# batsim1_1.net
KiCad netlist of a schematic drawn in EAGLE
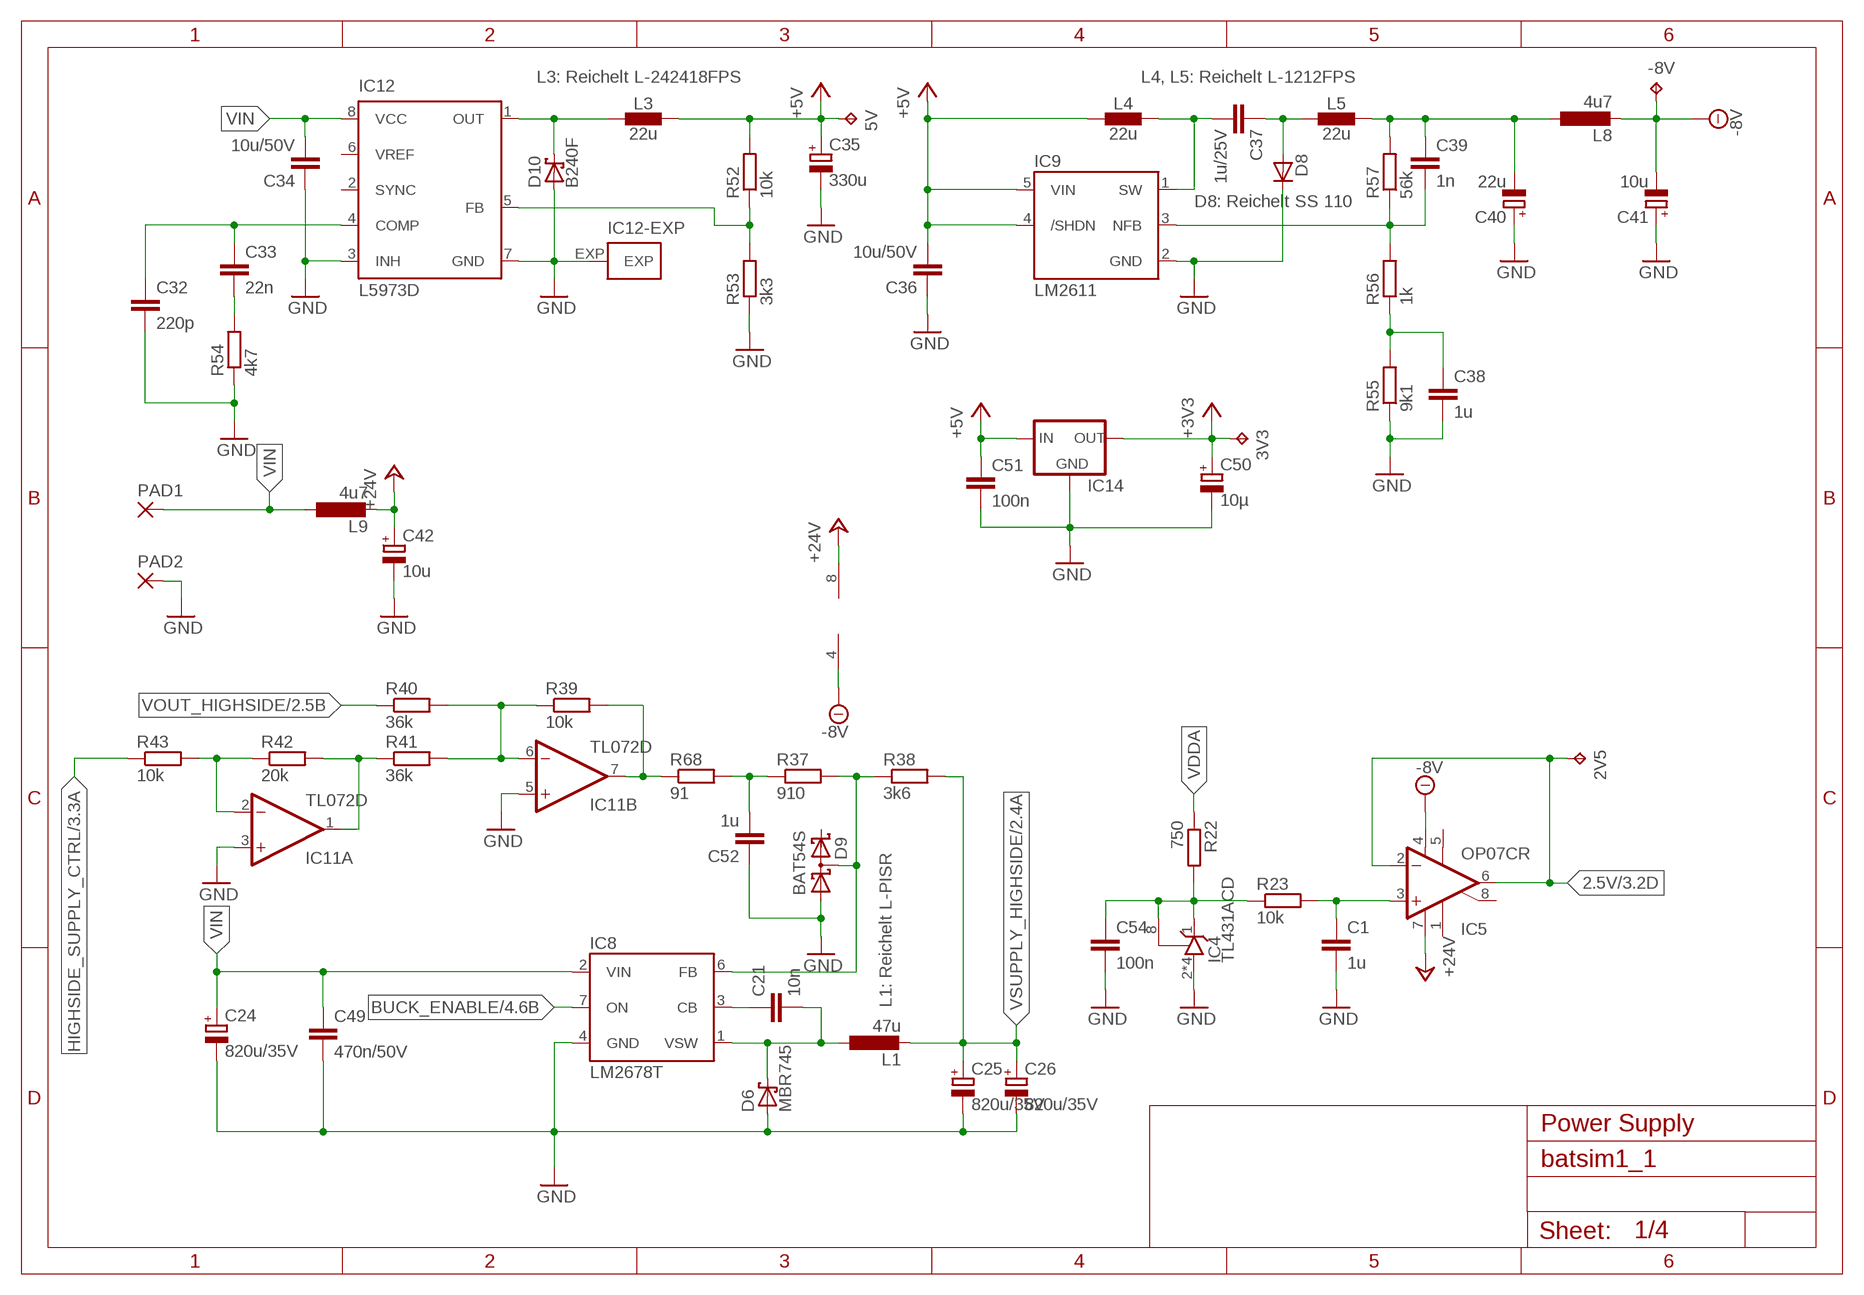
[diagram p0: schematic, sheet 1]
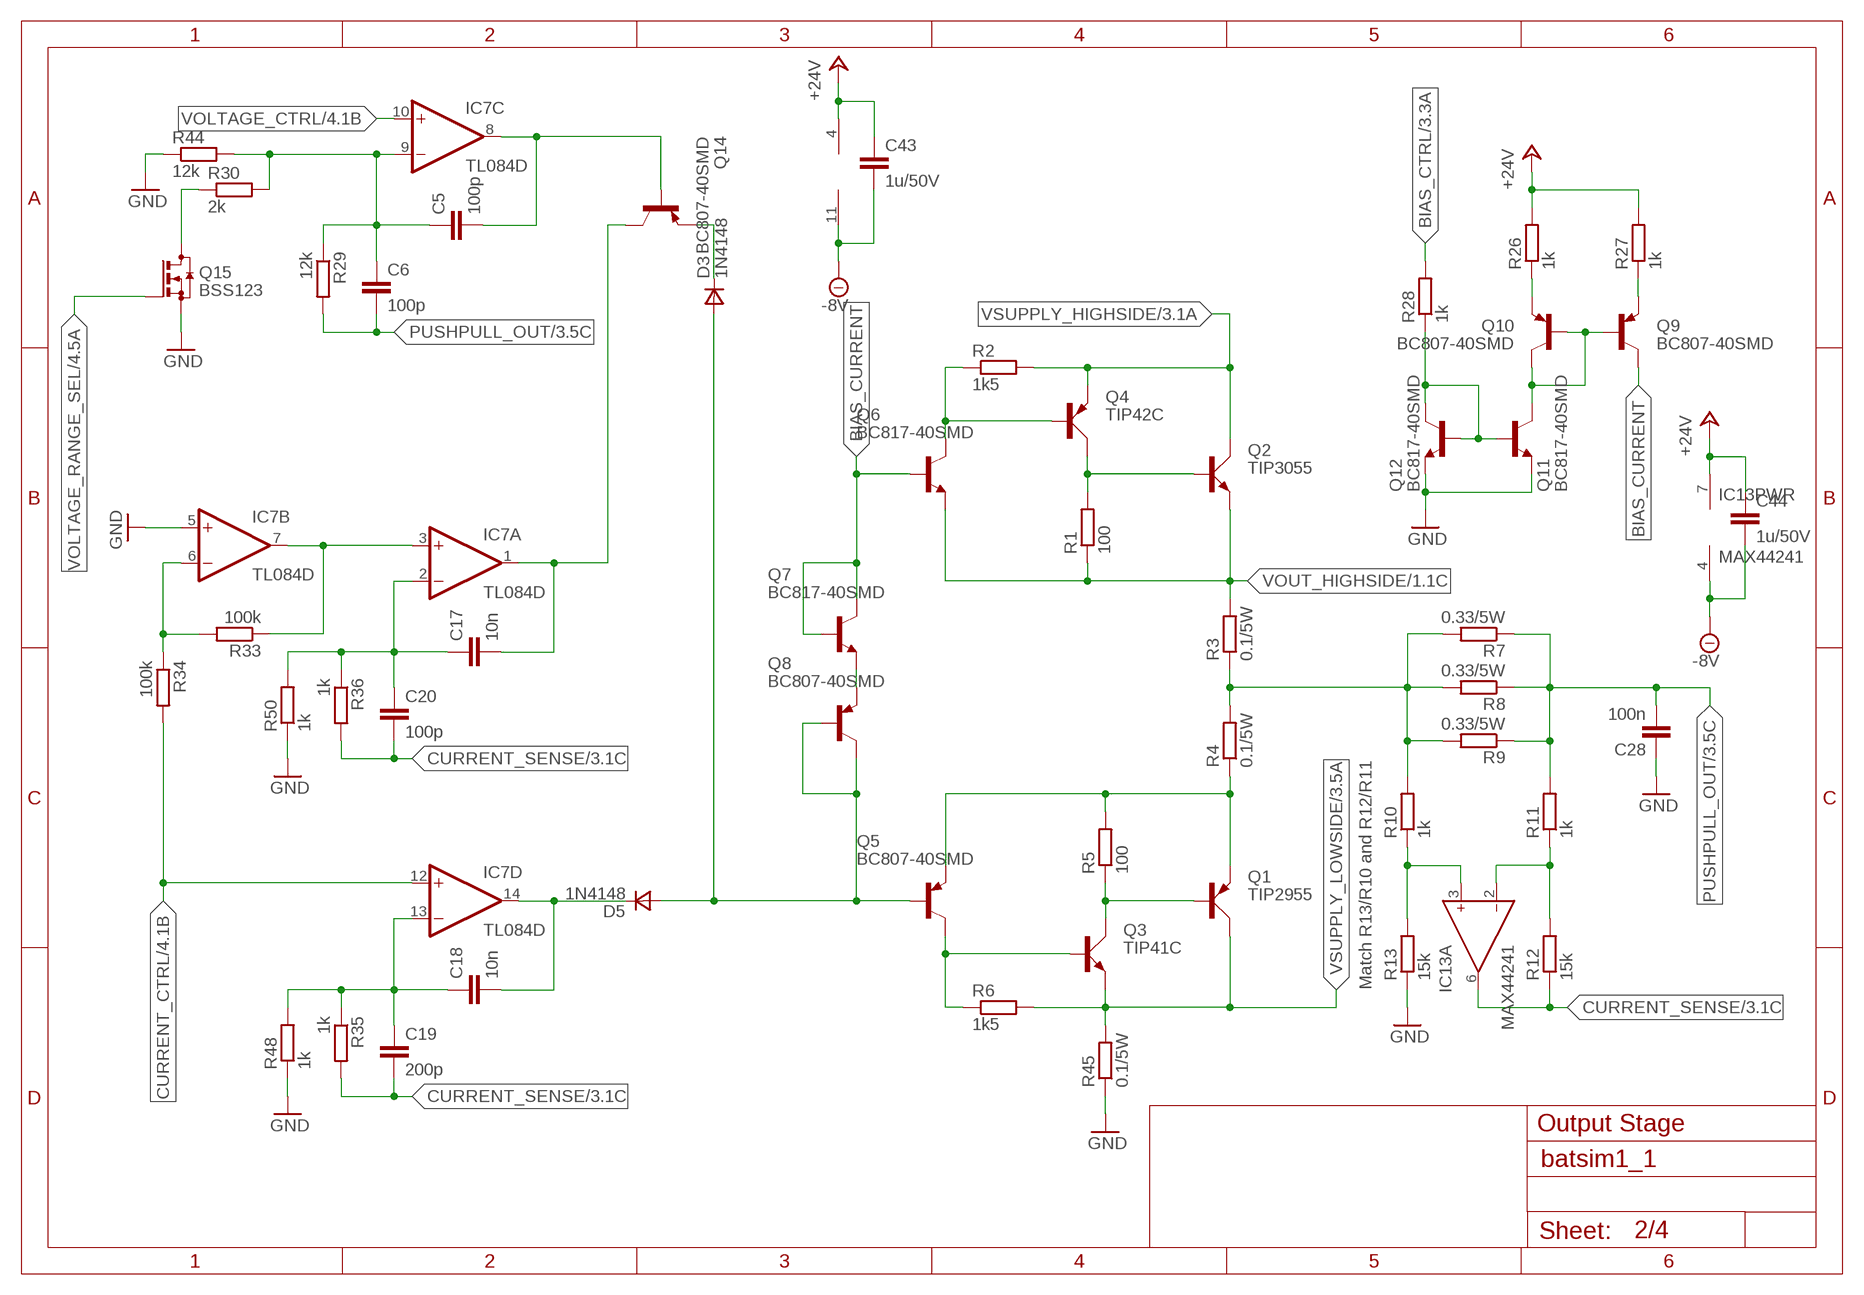
[diagram p1: schematic, sheet 2]
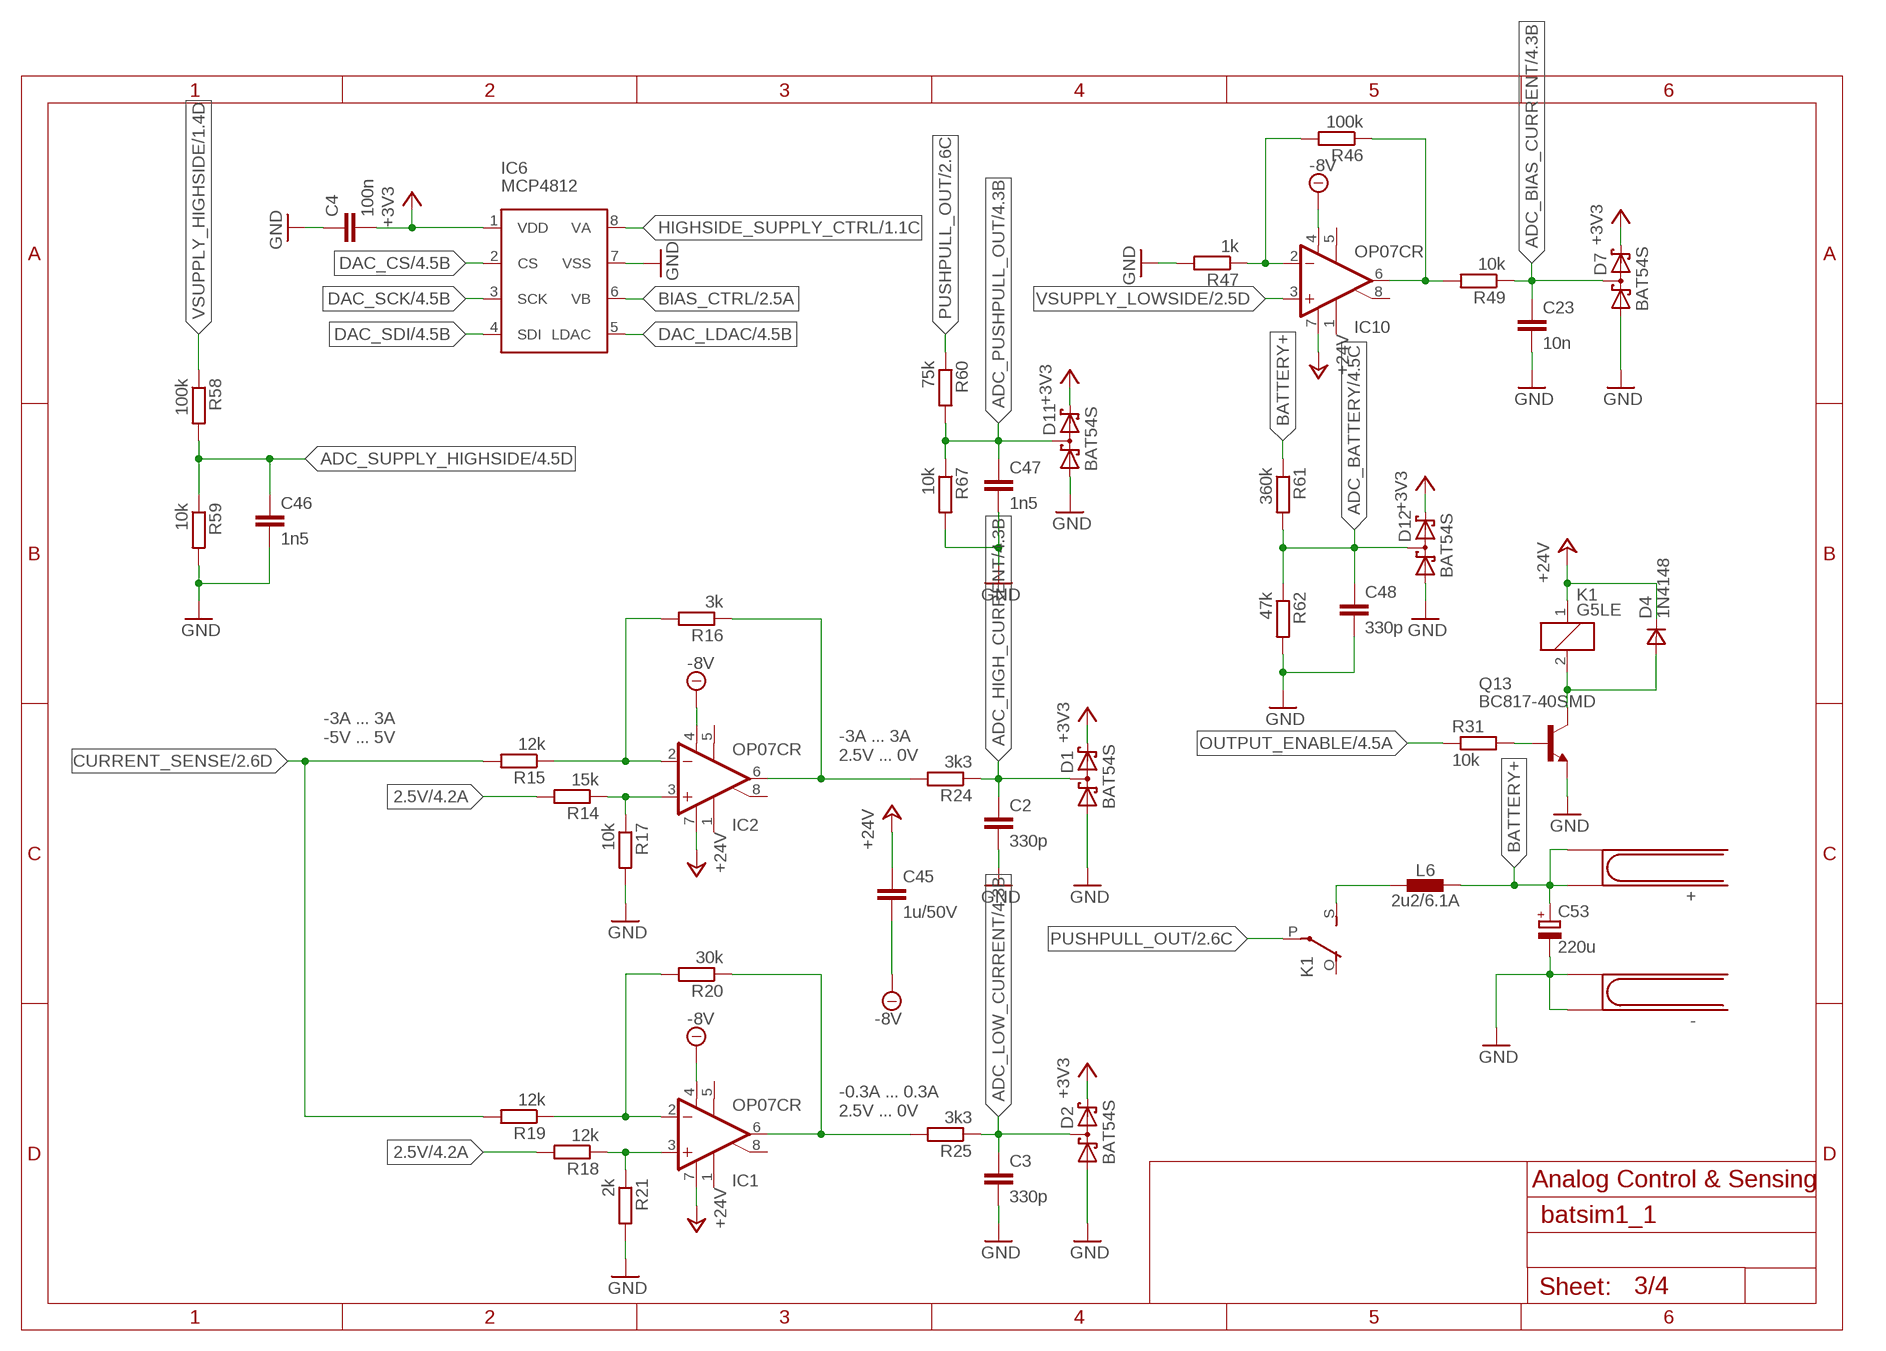
[diagram p2: schematic, sheet 3]
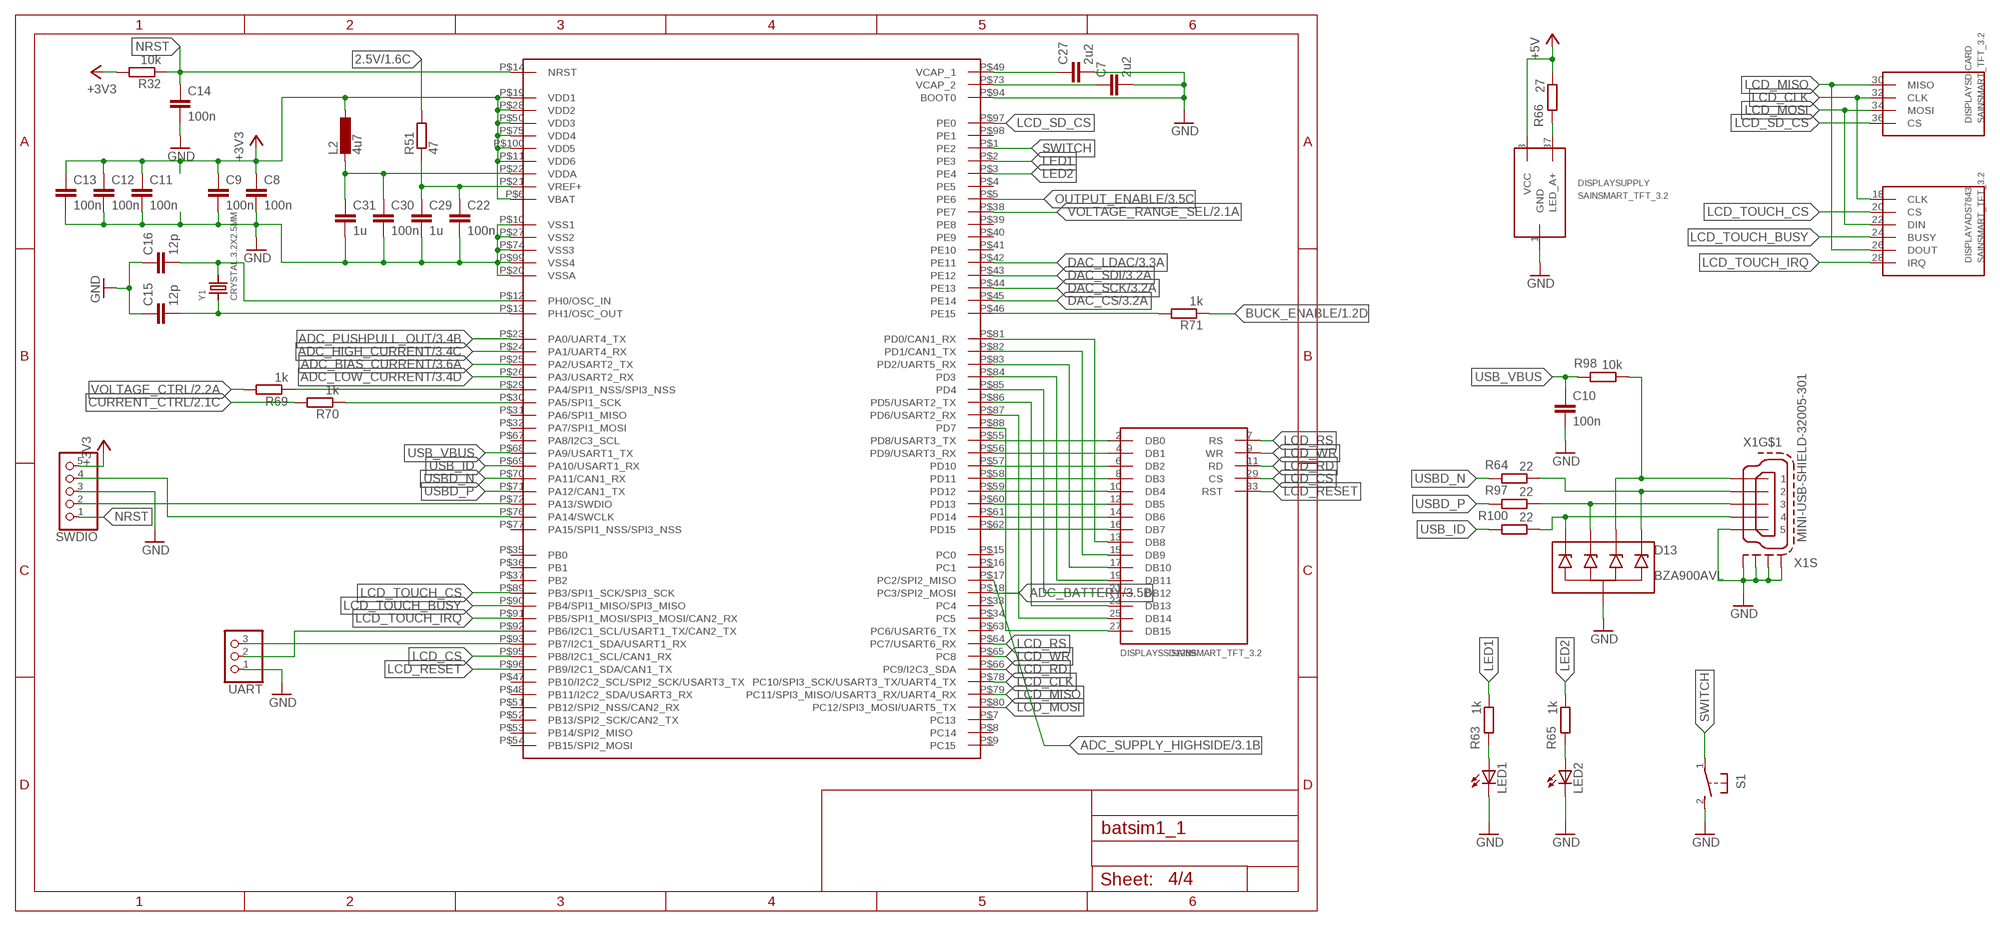
[diagram p3: schematic, sheet 4]

(export (version "E")
  (design (tool "Eeschema 10.0.6"))
  (components
    (comp (ref "+")
      (value "4MMJACK")
      (footprint "eagle-import:4MMJACK")
      (libsource (lib "eagle-import") (part "4MMJACK"))
    )
    (comp (ref "-")
      (value "4MMJACK")
      (footprint "eagle-import:4MMJACK")
      (libsource (lib "eagle-import") (part "4MMJACK"))
    )
    (comp (ref "C2")
      (value "330p")
      (footprint "eagle-import:C0603")
      (libsource (lib "eagle-import") (part "C-EUC0603"))
    )
    (comp (ref "C3")
      (value "330p")
      (footprint "eagle-import:C0603")
      (libsource (lib "eagle-import") (part "C-EUC0603"))
    )
    (comp (ref "C4")
      (value "100n")
      (footprint "eagle-import:C0603")
      (libsource (lib "eagle-import") (part "C-EUC0603"))
    )
    (comp (ref "C23")
      (value "10n")
      (footprint "eagle-import:C0603")
      (libsource (lib "eagle-import") (part "C-EUC0603"))
    )
    (comp (ref "C45")
      (value "1u/50V")
      (footprint "eagle-import:C0603")
      (libsource (lib "eagle-import") (part "C-EUC0603"))
    )
    (comp (ref "C46")
      (value "1n5")
      (footprint "eagle-import:C0603")
      (libsource (lib "eagle-import") (part "C-EUC0603"))
    )
    (comp (ref "C47")
      (value "1n5")
      (footprint "eagle-import:C0603")
      (libsource (lib "eagle-import") (part "C-EUC0603"))
    )
    (comp (ref "C48")
      (value "330p")
      (footprint "eagle-import:C0603")
      (libsource (lib "eagle-import") (part "C-EUC0603"))
    )
    (comp (ref "C53")
      (value "220u")
      (footprint "eagle-import:E5-10,5")
      (libsource (lib "eagle-import") (part "resistor_CPOL-EUE5-10.5"))
    )
    (comp (ref "D1")
      (value "BAT54S")
      (footprint "eagle-import:SOT23")
      (libsource (lib "eagle-import") (part "BAT54S"))
    )
    (comp (ref "D2")
      (value "BAT54S")
      (footprint "eagle-import:SOT23")
      (libsource (lib "eagle-import") (part "BAT54S"))
    )
    (comp (ref "D4")
      (value "1N4148")
      (footprint "eagle-import:SOD323")
      (fields (field (name "MPN") "CDSOD323-T05C"))
      (libsource (lib "eagle-import") (part "DSOD323"))
    )
    (comp (ref "D7")
      (value "BAT54S")
      (footprint "eagle-import:SOT23")
      (libsource (lib "eagle-import") (part "BAT54S"))
    )
    (comp (ref "D11")
      (value "BAT54S")
      (footprint "eagle-import:SOT23")
      (libsource (lib "eagle-import") (part "BAT54S"))
    )
    (comp (ref "D12")
      (value "BAT54S")
      (footprint "eagle-import:SOT23")
      (libsource (lib "eagle-import") (part "BAT54S"))
    )
    (comp (ref "IC1")
      (value "OP07CR")
      (footprint "eagle-import:SO08")
      (libsource (lib "eagle-import") (part "OP07RC"))
    )
    (comp (ref "IC2")
      (value "OP07CR")
      (footprint "eagle-import:SO08")
      (libsource (lib "eagle-import") (part "OP07RC"))
    )
    (comp (ref "IC6")
      (value "MCP4812")
      (footprint "eagle-import:SO08")
      (fields (field (name "MPN") "MCP4822-E/SN"))
      (libsource (lib "eagle-import") (part "MCP4812"))
    )
    (comp (ref "IC10")
      (value "OP07CR")
      (footprint "eagle-import:SO08")
      (libsource (lib "eagle-import") (part "OP07RC"))
    )
    (comp (ref "K1")
      (value "G5LE")
      (footprint "eagle-import:G5LE")
      (libsource (lib "eagle-import") (part "G5LE"))
    )
    (comp (ref "L6")
      (value "2u2/6.1A")
      (footprint "eagle-import:L_NR60XX")
      (libsource (lib "eagle-import") (part "INDUCTOR-NR60XX"))
    )
    (comp (ref "Q13")
      (value "BC817-40SMD")
      (footprint "eagle-import:SOT23-BEC")
      (libsource (lib "eagle-import") (part "BC817SMD-40"))
    )
    (comp (ref "R14")
      (value "15k")
      (footprint "eagle-import:R0603")
      (libsource (lib "eagle-import") (part "R-EU_R0603"))
    )
    (comp (ref "R15")
      (value "12k")
      (footprint "eagle-import:R0603")
      (libsource (lib "eagle-import") (part "R-EU_R0603"))
    )
    (comp (ref "R16")
      (value "3k")
      (footprint "eagle-import:R0603")
      (libsource (lib "eagle-import") (part "R-EU_R0603"))
    )
    (comp (ref "R17")
      (value "10k")
      (footprint "eagle-import:R0603")
      (libsource (lib "eagle-import") (part "R-EU_R0603"))
    )
    (comp (ref "R18")
      (value "12k")
      (footprint "eagle-import:R0603")
      (libsource (lib "eagle-import") (part "R-EU_R0603"))
    )
    (comp (ref "R19")
      (value "12k")
      (footprint "eagle-import:R0603")
      (libsource (lib "eagle-import") (part "R-EU_R0603"))
    )
    (comp (ref "R20")
      (value "30k")
      (footprint "eagle-import:R0603")
      (libsource (lib "eagle-import") (part "R-EU_R0603"))
    )
    (comp (ref "R21")
      (value "2k")
      (footprint "eagle-import:R0603")
      (libsource (lib "eagle-import") (part "R-EU_R0603"))
    )
    (comp (ref "R24")
      (value "3k3")
      (footprint "eagle-import:R0603")
      (libsource (lib "eagle-import") (part "R-EU_R0603"))
    )
    (comp (ref "R25")
      (value "3k3")
      (footprint "eagle-import:R0603")
      (libsource (lib "eagle-import") (part "R-EU_R0603"))
    )
    (comp (ref "R31")
      (value "10k")
      (footprint "eagle-import:R0603")
      (libsource (lib "eagle-import") (part "R-EU_R0603"))
    )
    (comp (ref "R46")
      (value "100k")
      (footprint "eagle-import:R0603")
      (libsource (lib "eagle-import") (part "R-EU_R0603"))
    )
    (comp (ref "R47")
      (value "1k")
      (footprint "eagle-import:R0603")
      (libsource (lib "eagle-import") (part "R-EU_R0603"))
    )
    (comp (ref "R49")
      (value "10k")
      (footprint "eagle-import:R0603")
      (libsource (lib "eagle-import") (part "R-EU_R0603"))
    )
    (comp (ref "R58")
      (value "100k")
      (footprint "eagle-import:R0603")
      (libsource (lib "eagle-import") (part "R-EU_R0603"))
    )
    (comp (ref "R59")
      (value "10k")
      (footprint "eagle-import:R0603")
      (libsource (lib "eagle-import") (part "R-EU_R0603"))
    )
    (comp (ref "R60")
      (value "75k")
      (footprint "eagle-import:R0603")
      (libsource (lib "eagle-import") (part "R-EU_R0603"))
    )
    (comp (ref "R61")
      (value "360k")
      (footprint "eagle-import:R0603")
      (libsource (lib "eagle-import") (part "R-EU_R0603"))
    )
    (comp (ref "R62")
      (value "47k")
      (footprint "eagle-import:R0603")
      (libsource (lib "eagle-import") (part "R-EU_R0603"))
    )
    (comp (ref "R67")
      (value "10k")
      (footprint "eagle-import:R0603")
      (libsource (lib "eagle-import") (part "R-EU_R0603"))
    )
    (comp (ref "C7")
      (value "2u2")
      (footprint "eagle-import:C1206")
      (libsource (lib "eagle-import") (part "C-EUC1206"))
    )
    (comp (ref "C8")
      (value "100n")
      (footprint "eagle-import:C0603")
      (libsource (lib "eagle-import") (part "C-EUC0603"))
    )
    (comp (ref "C9")
      (value "100n")
      (footprint "eagle-import:C0603")
      (libsource (lib "eagle-import") (part "C-EUC0603"))
    )
    (comp (ref "C10")
      (value "100n")
      (footprint "eagle-import:C0603K")
      (libsource (lib "eagle-import") (part "C-EUC0603K"))
    )
    (comp (ref "C11")
      (value "100n")
      (footprint "eagle-import:C0603")
      (libsource (lib "eagle-import") (part "C-EUC0603"))
    )
    (comp (ref "C12")
      (value "100n")
      (footprint "eagle-import:C0603")
      (libsource (lib "eagle-import") (part "C-EUC0603"))
    )
    (comp (ref "C13")
      (value "100n")
      (footprint "eagle-import:C0603")
      (libsource (lib "eagle-import") (part "C-EUC0603"))
    )
    (comp (ref "C14")
      (value "100n")
      (footprint "eagle-import:C0603")
      (libsource (lib "eagle-import") (part "C-EUC0603"))
    )
    (comp (ref "C15")
      (value "12p")
      (footprint "eagle-import:C0603")
      (libsource (lib "eagle-import") (part "C-EUC0603"))
    )
    (comp (ref "C16")
      (value "12p")
      (footprint "eagle-import:C0603")
      (libsource (lib "eagle-import") (part "C-EUC0603"))
    )
    (comp (ref "C22")
      (value "100n")
      (footprint "eagle-import:C0603")
      (libsource (lib "eagle-import") (part "C-EUC0603"))
    )
    (comp (ref "C27")
      (value "2u2")
      (footprint "eagle-import:C1206")
      (libsource (lib "eagle-import") (part "C-EUC1206"))
    )
    (comp (ref "C29")
      (value "1u")
      (footprint "eagle-import:C0603")
      (libsource (lib "eagle-import") (part "C-EUC0603"))
    )
    (comp (ref "C30")
      (value "100n")
      (footprint "eagle-import:C0603")
      (libsource (lib "eagle-import") (part "C-EUC0603"))
    )
    (comp (ref "C31")
      (value "1u")
      (footprint "eagle-import:C0603")
      (libsource (lib "eagle-import") (part "C-EUC0603"))
    )
    (comp (ref "D13")
      (value "BZA900AVL")
      (footprint "eagle-import:SOT-665")
      (libsource (lib "eagle-import") (part "BZA900AVL"))
    )
    (comp (ref "DISPLAY")
      (value "SAINSMART_TFT_3.2")
      (footprint "eagle-import:SAINSMART_TFT_3.2")
      (libsource (lib "eagle-import") (part "SAINSMART_TFT_3.2"))
    )
    (comp (ref "L2")
      (value "4u7")
      (footprint "eagle-import:L2012C")
      (libsource (lib "eagle-import") (part "L-EUL2012C"))
    )
    (comp (ref "LED1")
      (value "LEDCHIP-LED0603")
      (footprint "eagle-import:CHIP-LED0603")
      (libsource (lib "eagle-import") (part "LEDCHIP-LED0603"))
    )
    (comp (ref "LED2")
      (value "LEDCHIP-LED0603")
      (footprint "eagle-import:CHIP-LED0603")
      (libsource (lib "eagle-import") (part "LEDCHIP-LED0603"))
    )
    (comp (ref "R32")
      (value "10k")
      (footprint "eagle-import:R0603")
      (libsource (lib "eagle-import") (part "R-EU_R0603"))
    )
    (comp (ref "R51")
      (value "47")
      (footprint "eagle-import:R0603")
      (libsource (lib "eagle-import") (part "R-EU_R0603"))
    )
    (comp (ref "R63")
      (value "1k")
      (footprint "eagle-import:R0603")
      (libsource (lib "eagle-import") (part "R-EU_R0603"))
    )
    (comp (ref "R64")
      (value "22")
      (footprint "eagle-import:R0603")
      (libsource (lib "eagle-import") (part "R-EU_R0603"))
    )
    (comp (ref "R65")
      (value "1k")
      (footprint "eagle-import:R0603")
      (libsource (lib "eagle-import") (part "R-EU_R0603"))
    )
    (comp (ref "R66")
      (value "27")
      (footprint "eagle-import:R0603")
      (libsource (lib "eagle-import") (part "R-EU_R0603"))
    )
    (comp (ref "R69")
      (value "1k")
      (footprint "eagle-import:R0603")
      (libsource (lib "eagle-import") (part "R-EU_R0603"))
    )
    (comp (ref "R70")
      (value "1k")
      (footprint "eagle-import:R0603")
      (libsource (lib "eagle-import") (part "R-EU_R0603"))
    )
    (comp (ref "R71")
      (value "1k")
      (footprint "eagle-import:R0603")
      (libsource (lib "eagle-import") (part "R-EU_R0603"))
    )
    (comp (ref "R97")
      (value "22")
      (footprint "eagle-import:R0603")
      (libsource (lib "eagle-import") (part "R-EU_R0603"))
    )
    (comp (ref "R98")
      (value "10k")
      (footprint "eagle-import:R0603")
      (libsource (lib "eagle-import") (part "R-EU_R0603"))
    )
    (comp (ref "R100")
      (value "22")
      (footprint "eagle-import:R0603")
      (libsource (lib "eagle-import") (part "R-EU_R0603"))
    )
    (comp (ref "S1")
      (value "31-XX")
      (footprint "eagle-import:B3F-31XX")
      (fields (field (name "MPN") "B3F-3100"))
      (libsource (lib "eagle-import") (part "31-XX"))
    )
    (comp (ref "SWDIO")
      (value "PINHD-1X5")
      (footprint "eagle-import:1X05")
      (libsource (lib "eagle-import") (part "PINHD-1X5"))
    )
    (comp (ref "U$1")
      (value "STM32F407X100")
      (footprint "eagle-import:LQFP100_14")
      (libsource (lib "eagle-import") (part "STM32F407X100"))
    )
    (comp (ref "UART")
      (value "PINHD-1X3")
      (footprint "eagle-import:1X03")
      (libsource (lib "eagle-import") (part "PINHD-1X3"))
    )
    (comp (ref "X1")
      (value "MINI-USB-SHIELD-32005-301")
      (footprint "eagle-import:32005-301")
      (libsource (lib "eagle-import") (part "MINI-USB-SCHIELD-32005-301"))
    )
    (comp (ref "Y1")
      (value "CRYSTAL.3.2X2.5MM")
      (footprint "eagle-import:3.2X2.5MM")
      (libsource (lib "eagle-import") (part "CRYSTAL.3.2X2.5MM"))
    )
    (comp (ref "C5")
      (value "100p")
      (footprint "eagle-import:C0603")
      (libsource (lib "eagle-import") (part "C-EUC0603"))
    )
    (comp (ref "C6")
      (value "100p")
      (footprint "eagle-import:C0603")
      (libsource (lib "eagle-import") (part "C-EUC0603"))
    )
    (comp (ref "C17")
      (value "10n")
      (footprint "eagle-import:C0603")
      (libsource (lib "eagle-import") (part "C-EUC0603"))
    )
    (comp (ref "C18")
      (value "10n")
      (footprint "eagle-import:C0603")
      (libsource (lib "eagle-import") (part "C-EUC0603"))
    )
    (comp (ref "C19")
      (value "200p")
      (footprint "eagle-import:C0603")
      (libsource (lib "eagle-import") (part "C-EUC0603"))
    )
    (comp (ref "C20")
      (value "100p")
      (footprint "eagle-import:C0603")
      (libsource (lib "eagle-import") (part "C-EUC0603"))
    )
    (comp (ref "C28")
      (value "100n")
      (footprint "eagle-import:C1206")
      (libsource (lib "eagle-import") (part "C-EUC1206"))
    )
    (comp (ref "C43")
      (value "1u/50V")
      (footprint "eagle-import:C0603")
      (libsource (lib "eagle-import") (part "C-EUC0603"))
    )
    (comp (ref "C44")
      (value "1u/50V")
      (footprint "eagle-import:C0603")
      (libsource (lib "eagle-import") (part "C-EUC0603"))
    )
    (comp (ref "D3")
      (value "1N4148")
      (footprint "eagle-import:SOD323")
      (fields (field (name "MPN") "CDSOD323-T05C"))
      (libsource (lib "eagle-import") (part "DSOD323"))
    )
    (comp (ref "D5")
      (value "1N4148")
      (footprint "eagle-import:SOD323")
      (fields (field (name "MPN") "CDSOD323-T05C"))
      (libsource (lib "eagle-import") (part "DSOD323"))
    )
    (comp (ref "IC7")
      (value "TL084D")
      (footprint "eagle-import:SO14")
      (libsource (lib "eagle-import") (part "TL084D"))
    )
    (comp (ref "IC13")
      (value "MAX44241")
      (footprint "eagle-import:UMAX8")
      (libsource (lib "eagle-import") (part "MAX44241"))
    )
    (comp (ref "Q1")
      (value "TIP2955")
      (footprint "eagle-import:TOP3AV")
      (libsource (lib "eagle-import") (part "TIP2955"))
    )
    (comp (ref "Q2")
      (value "TIP3055")
      (footprint "eagle-import:TOP3AV")
      (libsource (lib "eagle-import") (part "TIP3055"))
    )
    (comp (ref "Q3")
      (value "TIP41C")
      (footprint "eagle-import:TO220AV")
      (libsource (lib "eagle-import") (part "TIP41C"))
    )
    (comp (ref "Q4")
      (value "TIP42C")
      (footprint "eagle-import:TO220AV")
      (libsource (lib "eagle-import") (part "TIP42C"))
    )
    (comp (ref "Q5")
      (value "BC807-40SMD")
      (footprint "eagle-import:SOT23-BEC")
      (libsource (lib "eagle-import") (part "BC807SMD-40"))
    )
    (comp (ref "Q6")
      (value "BC817-40SMD")
      (footprint "eagle-import:SOT23-BEC")
      (libsource (lib "eagle-import") (part "BC817SMD-40"))
    )
    (comp (ref "Q7")
      (value "BC817-40SMD")
      (footprint "eagle-import:SOT23-BEC")
      (libsource (lib "eagle-import") (part "BC817SMD-40"))
    )
    (comp (ref "Q8")
      (value "BC807-40SMD")
      (footprint "eagle-import:SOT23-BEC")
      (libsource (lib "eagle-import") (part "BC807SMD-40"))
    )
    (comp (ref "Q9")
      (value "BC807-40SMD")
      (footprint "eagle-import:SOT23-BEC")
      (libsource (lib "eagle-import") (part "BC807SMD-40"))
    )
    (comp (ref "Q10")
      (value "BC807-40SMD")
      (footprint "eagle-import:SOT23-BEC")
      (libsource (lib "eagle-import") (part "BC807SMD-40"))
    )
    (comp (ref "Q11")
      (value "BC817-40SMD")
      (footprint "eagle-import:SOT23-BEC")
      (libsource (lib "eagle-import") (part "BC817SMD-40"))
    )
    (comp (ref "Q12")
      (value "BC817-40SMD")
      (footprint "eagle-import:SOT23-BEC")
      (libsource (lib "eagle-import") (part "BC817SMD-40"))
    )
    (comp (ref "Q14")
      (value "BC807-40SMD")
      (footprint "eagle-import:SOT23-BEC")
      (libsource (lib "eagle-import") (part "BC807SMD-40"))
    )
    (comp (ref "Q15")
      (value "BSS123")
      (footprint "eagle-import:SOT23")
      (libsource (lib "eagle-import") (part "BSS123"))
    )
    (comp (ref "R1")
      (value "100")
      (footprint "eagle-import:R0603")
      (libsource (lib "eagle-import") (part "R-EU_R0603"))
    )
    (comp (ref "R2")
      (value "1k5")
      (footprint "eagle-import:R0603")
      (libsource (lib "eagle-import") (part "R-EU_R0603"))
    )
    (comp (ref "R3")
      (value "0.1/5W")
      (footprint "eagle-import:5WAXIAL")
      (libsource (lib "eagle-import") (part "5WAXIAL"))
    )
    (comp (ref "R4")
      (value "0.1/5W")
      (footprint "eagle-import:5WAXIAL")
      (libsource (lib "eagle-import") (part "5WAXIAL"))
    )
    (comp (ref "R5")
      (value "100")
      (footprint "eagle-import:R0603")
      (libsource (lib "eagle-import") (part "R-EU_R0603"))
    )
    (comp (ref "R6")
      (value "1k5")
      (footprint "eagle-import:R0603")
      (libsource (lib "eagle-import") (part "R-EU_R0603"))
    )
    (comp (ref "R7")
      (value "0.33/5W")
      (footprint "eagle-import:5WAXIAL")
      (libsource (lib "eagle-import") (part "5WAXIAL"))
    )
    (comp (ref "R8")
      (value "0.33/5W")
      (footprint "eagle-import:5WAXIAL")
      (libsource (lib "eagle-import") (part "5WAXIAL"))
    )
    (comp (ref "R9")
      (value "0.33/5W")
      (footprint "eagle-import:5WAXIAL")
      (libsource (lib "eagle-import") (part "5WAXIAL"))
    )
    (comp (ref "R10")
      (value "1k")
      (footprint "eagle-import:R0603")
      (libsource (lib "eagle-import") (part "R-EU_R0603"))
    )
    (comp (ref "R11")
      (value "1k")
      (footprint "eagle-import:R0603")
      (libsource (lib "eagle-import") (part "R-EU_R0603"))
    )
    (comp (ref "R12")
      (value "15k")
      (footprint "eagle-import:R0603")
      (libsource (lib "eagle-import") (part "R-EU_R0603"))
    )
    (comp (ref "R13")
      (value "15k")
      (footprint "eagle-import:R0603")
      (libsource (lib "eagle-import") (part "R-EU_R0603"))
    )
    (comp (ref "R26")
      (value "1k")
      (footprint "eagle-import:R0603")
      (libsource (lib "eagle-import") (part "R-EU_R0603"))
    )
    (comp (ref "R27")
      (value "1k")
      (footprint "eagle-import:R0603")
      (libsource (lib "eagle-import") (part "R-EU_R0603"))
    )
    (comp (ref "R28")
      (value "1k")
      (footprint "eagle-import:R0603")
      (libsource (lib "eagle-import") (part "R-EU_R0603"))
    )
    (comp (ref "R29")
      (value "12k")
      (footprint "eagle-import:R0603")
      (libsource (lib "eagle-import") (part "R-EU_R0603"))
    )
    (comp (ref "R30")
      (value "2k")
      (footprint "eagle-import:R0603")
      (libsource (lib "eagle-import") (part "R-EU_R0603"))
    )
    (comp (ref "R33")
      (value "100k")
      (footprint "eagle-import:R0603")
      (libsource (lib "eagle-import") (part "R-EU_R0603"))
    )
    (comp (ref "R34")
      (value "100k")
      (footprint "eagle-import:R0603")
      (libsource (lib "eagle-import") (part "R-EU_R0603"))
    )
    (comp (ref "R35")
      (value "1k")
      (footprint "eagle-import:R0603")
      (libsource (lib "eagle-import") (part "R-EU_R0603"))
    )
    (comp (ref "R36")
      (value "1k")
      (footprint "eagle-import:R0603")
      (libsource (lib "eagle-import") (part "R-EU_R0603"))
    )
    (comp (ref "R44")
      (value "12k")
      (footprint "eagle-import:R0603")
      (libsource (lib "eagle-import") (part "R-EU_R0603"))
    )
    (comp (ref "R45")
      (value "0.1/5W")
      (footprint "eagle-import:5WAXIAL")
      (libsource (lib "eagle-import") (part "5WAXIAL"))
    )
    (comp (ref "R48")
      (value "1k")
      (footprint "eagle-import:R0603")
      (libsource (lib "eagle-import") (part "R-EU_R0603"))
    )
    (comp (ref "R50")
      (value "1k")
      (footprint "eagle-import:R0603")
      (libsource (lib "eagle-import") (part "R-EU_R0603"))
    )
    (comp (ref "-8V")
      (value "TPB1,27")
      (footprint "eagle-import:B1,27")
      (libsource (lib "eagle-import") (part "TPB1,27"))
    )
    (comp (ref "2V5")
      (value "TPB1,27")
      (footprint "eagle-import:B1,27")
      (libsource (lib "eagle-import") (part "TPB1,27"))
    )
    (comp (ref "3V3")
      (value "TPB1,27")
      (footprint "eagle-import:B1,27")
      (libsource (lib "eagle-import") (part "TPB1,27"))
    )
    (comp (ref "5V")
      (value "TPB1,27")
      (footprint "eagle-import:B1,27")
      (libsource (lib "eagle-import") (part "TPB1,27"))
    )
    (comp (ref "C1")
      (value "1u")
      (footprint "eagle-import:C0603")
      (libsource (lib "eagle-import") (part "C-EUC0603"))
    )
    (comp (ref "C21")
      (value "10n")
      (footprint "eagle-import:C0603")
      (libsource (lib "eagle-import") (part "C-EUC0603"))
    )
    (comp (ref "C24")
      (value "820u/35V")
      (footprint "eagle-import:E5-10,5")
      (libsource (lib "eagle-import") (part "resistor_CPOL-EUE5-10.5"))
    )
    (comp (ref "C25")
      (value "820u/35V")
      (footprint "eagle-import:E5-10,5")
      (libsource (lib "eagle-import") (part "resistor_CPOL-EUE5-10.5"))
    )
    (comp (ref "C26")
      (value "820u/35V")
      (footprint "eagle-import:E5-10,5")
      (libsource (lib "eagle-import") (part "resistor_CPOL-EUE5-10.5"))
    )
    (comp (ref "C32")
      (value "220p")
      (footprint "eagle-import:C0603")
      (libsource (lib "eagle-import") (part "C-EUC0603"))
    )
    (comp (ref "C33")
      (value "22n")
      (footprint "eagle-import:C0603")
      (libsource (lib "eagle-import") (part "C-EUC0603"))
    )
    (comp (ref "C34")
      (value "10u/50V")
      (footprint "eagle-import:C1206")
      (libsource (lib "eagle-import") (part "C-EUC1206"))
    )
    (comp (ref "C35")
      (value "330u")
      (footprint "eagle-import:153CLV-0605")
      (libsource (lib "eagle-import") (part "resistor_CPOL-EU153CLV-0605"))
    )
    (comp (ref "C36")
      (value "10u/50V")
      (footprint "eagle-import:C1206")
      (libsource (lib "eagle-import") (part "C-EUC1206"))
    )
    (comp (ref "C37")
      (value "1u/25V")
      (footprint "eagle-import:C1206")
      (libsource (lib "eagle-import") (part "C-EUC1206"))
    )
    (comp (ref "C38")
      (value "1u")
      (footprint "eagle-import:C0603")
      (libsource (lib "eagle-import") (part "C-EUC0603"))
    )
    (comp (ref "C39")
      (value "1n")
      (footprint "eagle-import:C0603")
      (libsource (lib "eagle-import") (part "C-EUC0603"))
    )
    (comp (ref "C40")
      (value "22u")
      (footprint "eagle-import:153CLV-0505")
      (libsource (lib "eagle-import") (part "resistor_CPOL-EU153CLV-0505"))
    )
    (comp (ref "C41")
      (value "10u")
      (footprint "eagle-import:153CLV-0405")
      (libsource (lib "eagle-import") (part "resistor_CPOL-EU153CLV-0405"))
    )
    (comp (ref "C42")
      (value "10u")
      (footprint "eagle-import:153CLV-0505")
      (libsource (lib "eagle-import") (part "resistor_CPOL-EU153CLV-0505"))
    )
    (comp (ref "C49")
      (value "470n/50V")
      (footprint "eagle-import:C1206")
      (libsource (lib "eagle-import") (part "C-EUC1206"))
    )
    (comp (ref "C50")
      (value "10µ")
      (footprint "eagle-import:SMC_A")
      (libsource (lib "eagle-import") (part "CPOL-EUSMCA"))
    )
    (comp (ref "C51")
      (value "100n")
      (footprint "eagle-import:C0603")
      (libsource (lib "eagle-import") (part "C-EUC0603"))
    )
    (comp (ref "C52")
      (value "1u")
      (footprint "eagle-import:C0603")
      (libsource (lib "eagle-import") (part "C-EUC0603"))
    )
    (comp (ref "C54")
      (value "100n")
      (footprint "eagle-import:C0603")
      (libsource (lib "eagle-import") (part "C-EUC0603"))
    )
    (comp (ref "D6")
      (value "MBR745")
      (footprint "eagle-import:TO220ACS")
      (libsource (lib "eagle-import") (part "MBR745"))
    )
    (comp (ref "D8")
      (value "D-SMA")
      (footprint "eagle-import:SMA")
      (libsource (lib "eagle-import") (part "D-SMA"))
    )
    (comp (ref "D9")
      (value "BAT54S")
      (footprint "eagle-import:SOT23")
      (libsource (lib "eagle-import") (part "BAT54S"))
    )
    (comp (ref "D10")
      (value "B240F")
      (footprint "eagle-import:SMB")
      (libsource (lib "eagle-import") (part "SCHOTTKY-DIODESMD"))
    )
    (comp (ref "IC4")
      (value "TL431ACD")
      (footprint "eagle-import:SO8")
      (libsource (lib "eagle-import") (part "TL431ACD"))
    )
    (comp (ref "IC5")
      (value "OP07CR")
      (footprint "eagle-import:SO08")
      (libsource (lib "eagle-import") (part "OP07RC"))
    )
    (comp (ref "IC8")
      (value "LM2678T")
      (footprint "eagle-import:TO220-7")
      (libsource (lib "eagle-import") (part "LM2678T"))
    )
    (comp (ref "IC9")
      (value "LM2611")
      (footprint "eagle-import:SOT23-5")
      (libsource (lib "eagle-import") (part "LM2611"))
    )
    (comp (ref "IC11")
      (value "TL072D")
      (footprint "eagle-import:SO08")
      (libsource (lib "eagle-import") (part "TL072D"))
    )
    (comp (ref "IC12")
      (value "L5973D")
      (footprint "eagle-import:HSOP8")
      (fields (field (name "MF") "STMICROELECTRONICS"))
      (libsource (lib "eagle-import") (part "L5973D"))
    )
    (comp (ref "IC14")
      (value "LM1117")
      (footprint "eagle-import:SOT223")
      (libsource (lib "eagle-import") (part "LM1117"))
    )
    (comp (ref "L1")
      (value "47u")
      (footprint "eagle-import:PISR")
      (libsource (lib "eagle-import") (part "L-EUPISR"))
    )
    (comp (ref "L3")
      (value "22u")
      (footprint "eagle-import:L_NR60XX")
      (libsource (lib "eagle-import") (part "INDUCTOR-NR60XX"))
    )
    (comp (ref "L4")
      (value "22u")
      (footprint "eagle-import:L_1212")
      (libsource (lib "eagle-import") (part "INDUCTOR-1212"))
    )
    (comp (ref "L5")
      (value "22u")
      (footprint "eagle-import:L_1212")
      (libsource (lib "eagle-import") (part "INDUCTOR-1212"))
    )
    (comp (ref "L8")
      (value "4u7")
      (footprint "eagle-import:L2012C")
      (libsource (lib "eagle-import") (part "L-EUL2012C"))
    )
    (comp (ref "L9")
      (value "4u7")
      (footprint "eagle-import:L2012C")
      (libsource (lib "eagle-import") (part "L-EUL2012C"))
    )
    (comp (ref "PAD1")
      (value "3,81/1,4")
      (footprint "eagle-import:3,81_1,4")
      (libsource (lib "eagle-import") (part "3,81/1,4"))
    )
    (comp (ref "PAD2")
      (value "3,81/1,4")
      (footprint "eagle-import:3,81_1,4")
      (libsource (lib "eagle-import") (part "3,81/1,4"))
    )
    (comp (ref "R22")
      (value "750")
      (footprint "eagle-import:R0603")
      (libsource (lib "eagle-import") (part "R-EU_R0603"))
    )
    (comp (ref "R23")
      (value "10k")
      (footprint "eagle-import:R0603")
      (libsource (lib "eagle-import") (part "R-EU_R0603"))
    )
    (comp (ref "R37")
      (value "910")
      (footprint "eagle-import:R0603")
      (libsource (lib "eagle-import") (part "R-EU_R0603"))
    )
    (comp (ref "R38")
      (value "3k6")
      (footprint "eagle-import:R0603")
      (libsource (lib "eagle-import") (part "R-EU_R0603"))
    )
    (comp (ref "R39")
      (value "10k")
      (footprint "eagle-import:R0603")
      (libsource (lib "eagle-import") (part "R-EU_R0603"))
    )
    (comp (ref "R40")
      (value "36k")
      (footprint "eagle-import:R0603")
      (libsource (lib "eagle-import") (part "R-EU_R0603"))
    )
    (comp (ref "R41")
      (value "36k")
      (footprint "eagle-import:R0603")
      (libsource (lib "eagle-import") (part "R-EU_R0603"))
    )
    (comp (ref "R42")
      (value "20k")
      (footprint "eagle-import:R0603")
      (libsource (lib "eagle-import") (part "R-EU_R0603"))
    )
    (comp (ref "R43")
      (value "10k")
      (footprint "eagle-import:R0603")
      (libsource (lib "eagle-import") (part "R-EU_R0603"))
    )
    (comp (ref "R52")
      (value "10k")
      (footprint "eagle-import:R0603")
      (libsource (lib "eagle-import") (part "R-EU_R0603"))
    )
    (comp (ref "R53")
      (value "3k3")
      (footprint "eagle-import:R0603")
      (libsource (lib "eagle-import") (part "R-EU_R0603"))
    )
    (comp (ref "R54")
      (value "4k7")
      (footprint "eagle-import:R0603")
      (libsource (lib "eagle-import") (part "R-EU_R0603"))
    )
    (comp (ref "R55")
      (value "9k1")
      (footprint "eagle-import:R0603")
      (libsource (lib "eagle-import") (part "R-EU_R0603"))
    )
    (comp (ref "R56")
      (value "1k")
      (footprint "eagle-import:R0603")
      (libsource (lib "eagle-import") (part "R-EU_R0603"))
    )
    (comp (ref "R57")
      (value "56k")
      (footprint "eagle-import:R0603")
      (libsource (lib "eagle-import") (part "R-EU_R0603"))
    )
    (comp (ref "R68")
      (value "91")
      (footprint "eagle-import:R0603")
      (libsource (lib "eagle-import") (part "R-EU_R0603"))
    )
  )
  (nets
    (net (code "1") (name "+3V3") (class "Default")
      (node (ref "3V3") (pin "TP") (pinfunction "TP_TP") (pintype "input"))
      (node (ref "C11") (pin "1") (pinfunction "1_1") (pintype "passive"))
      (node (ref "C12") (pin "1") (pinfunction "1_1") (pintype "passive"))
      (node (ref "C13") (pin "1") (pinfunction "1_1") (pintype "passive"))
      (node (ref "C4") (pin "2") (pinfunction "2_2") (pintype "passive"))
      (node (ref "C50") (pin "+") (pinfunction "+_+") (pintype "passive"))
      (node (ref "C8") (pin "1") (pinfunction "1_1") (pintype "passive"))
      (node (ref "C9") (pin "1") (pinfunction "1_1") (pintype "passive"))
      (node (ref "D1") (pin "2") (pinfunction "C2_2") (pintype "passive"))
      (node (ref "D11") (pin "2") (pinfunction "C2_2") (pintype "passive"))
      (node (ref "D12") (pin "2") (pinfunction "C2_2") (pintype "passive"))
      (node (ref "D2") (pin "2") (pinfunction "C2_2") (pintype "passive"))
      (node (ref "D7") (pin "2") (pinfunction "C2_2") (pintype "passive"))
      (node (ref "IC14") (pin "2") (pinfunction "OUT_2") (pintype "passive"))
      (node (ref "IC6") (pin "1") (pinfunction "VDD_1") (pintype "bidirectional"))
      (node (ref "L2") (pin "1") (pinfunction "1_1") (pintype "passive"))
      (node (ref "R32") (pin "2") (pinfunction "2_2") (pintype "passive"))
      (node (ref "SWDIO") (pin "5") (pinfunction "5_5") (pintype "passive"))
      (node (ref "U$1") (pin "P$100") (pinfunction "VDD5_P$100") (pintype "bidirectional"))
      (node (ref "U$1") (pin "P$11") (pinfunction "VDD6_P$11") (pintype "bidirectional"))
      (node (ref "U$1") (pin "P$19") (pinfunction "VDD1_P$19") (pintype "bidirectional"))
      (node (ref "U$1") (pin "P$28") (pinfunction "VDD2_P$28") (pintype "bidirectional"))
      (node (ref "U$1") (pin "P$50") (pinfunction "VDD3_P$50") (pintype "bidirectional"))
      (node (ref "U$1") (pin "P$6") (pinfunction "VBAT_P$6") (pintype "bidirectional"))
      (node (ref "U$1") (pin "P$75") (pinfunction "VDD4_P$75") (pintype "bidirectional"))
    )
    (net (code "2") (name "+5V") (class "Default")
      (node (ref "5V") (pin "TP") (pinfunction "TP_TP") (pintype "input"))
      (node (ref "C35") (pin "+") (pinfunction "+_+") (pintype "passive"))
      (node (ref "C36") (pin "2") (pinfunction "2_2") (pintype "passive"))
      (node (ref "C51") (pin "1") (pinfunction "1_1") (pintype "passive"))
      (node (ref "DISPLAY") (pin "3") (pinfunction "VCC_3") (pintype "bidirectional"))
      (node (ref "IC14") (pin "3") (pinfunction "IN_3") (pintype "input"))
      (node (ref "IC9") (pin "4") (pinfunction "/SHDN_4") (pintype "input"))
      (node (ref "IC9") (pin "5") (pinfunction "VIN_5") (pintype "power_in"))
      (node (ref "L3") (pin "2") (pinfunction "2_2") (pintype "passive"))
      (node (ref "L4") (pin "1") (pinfunction "1_1") (pintype "passive"))
      (node (ref "R52") (pin "2") (pinfunction "2_2") (pintype "passive"))
      (node (ref "R66") (pin "1") (pinfunction "1_1") (pintype "passive"))
    )
    (net (code "3") (name "+24V") (class "Default")
      (node (ref "C42") (pin "+") (pinfunction "+_+") (pintype "passive"))
      (node (ref "C43") (pin "1") (pinfunction "1_1") (pintype "passive"))
      (node (ref "C44") (pin "1") (pinfunction "1_1") (pintype "passive"))
      (node (ref "C45") (pin "1") (pinfunction "1_1") (pintype "passive"))
      (node (ref "D4") (pin "1") (pinfunction "C_1") (pintype "passive"))
      (node (ref "IC1") (pin "7") (pinfunction "V+_7") (pintype "power_in"))
      (node (ref "IC10") (pin "7") (pinfunction "V+_7") (pintype "power_in"))
      (node (ref "IC11") (pin "8") (pinfunction "V+_8") (pintype "power_in"))
      (node (ref "IC13") (pin "7") (pinfunction "V+_7") (pintype "power_in"))
      (node (ref "IC2") (pin "7") (pinfunction "V+_7") (pintype "power_in"))
      (node (ref "IC5") (pin "7") (pinfunction "V+_7") (pintype "power_in"))
      (node (ref "IC7") (pin "4") (pinfunction "V+_4") (pintype "power_in"))
      (node (ref "K1") (pin "1") (pinfunction "1_1") (pintype "passive"))
      (node (ref "L9") (pin "2") (pinfunction "2_2") (pintype "passive"))
      (node (ref "R26") (pin "2") (pinfunction "2_2") (pintype "passive"))
      (node (ref "R27") (pin "2") (pinfunction "2_2") (pintype "passive"))
    )
    (net (code "4") (name "-8V") (class "Default")
      (node (ref "-8V") (pin "TP") (pinfunction "TP_TP") (pintype "input"))
      (node (ref "C41") (pin "-") (pinfunction "-_-") (pintype "passive"))
      (node (ref "C43") (pin "2") (pinfunction "2_2") (pintype "passive"))
      (node (ref "C44") (pin "2") (pinfunction "2_2") (pintype "passive"))
      (node (ref "C45") (pin "2") (pinfunction "2_2") (pintype "passive"))
      (node (ref "IC1") (pin "4") (pinfunction "V-_4") (pintype "power_in"))
      (node (ref "IC10") (pin "4") (pinfunction "V-_4") (pintype "power_in"))
      (node (ref "IC11") (pin "4") (pinfunction "V-_4") (pintype "power_in"))
      (node (ref "IC13") (pin "4") (pinfunction "V-_4") (pintype "power_in"))
      (node (ref "IC2") (pin "4") (pinfunction "V-_4") (pintype "power_in"))
      (node (ref "IC5") (pin "4") (pinfunction "V-_4") (pintype "power_in"))
      (node (ref "IC7") (pin "11") (pinfunction "V-_11") (pintype "power_in"))
      (node (ref "L8") (pin "2") (pinfunction "2_2") (pintype "passive"))
    )
    (net (code "5") (name "2.5V") (class "Default")
      (node (ref "2V5") (pin "TP") (pinfunction "TP_TP") (pintype "input"))
      (node (ref "IC5") (pin "2") (pinfunction "-IN_2") (pintype "input"))
      (node (ref "IC5") (pin "6") (pinfunction "OUT_6") (pintype "output"))
      (node (ref "R14") (pin "2") (pinfunction "2_2") (pintype "passive"))
      (node (ref "R18") (pin "2") (pinfunction "2_2") (pintype "passive"))
      (node (ref "R51") (pin "2") (pinfunction "2_2") (pintype "passive"))
    )
    (net (code "6") (name "ADC_BATTERY") (class "Default")
      (node (ref "C48") (pin "1") (pinfunction "1_1") (pintype "passive"))
      (node (ref "D12") (pin "3") (pinfunction "C1A2_3") (pintype "passive"))
      (node (ref "R61") (pin "2") (pinfunction "2_2") (pintype "passive"))
      (node (ref "R62") (pin "1") (pinfunction "1_1") (pintype "passive"))
      (node (ref "U$1") (pin "P$18") (pinfunction "PC3/SPI2_MOSI_P$18") (pintype "bidirectional"))
    )
    (net (code "7") (name "ADC_BIAS_CURRENT") (class "Default")
      (node (ref "C23") (pin "1") (pinfunction "1_1") (pintype "passive"))
      (node (ref "D7") (pin "3") (pinfunction "C1A2_3") (pintype "passive"))
      (node (ref "R49") (pin "1") (pinfunction "1_1") (pintype "passive"))
      (node (ref "U$1") (pin "P$25") (pinfunction "PA2/USART2_TX_P$25") (pintype "bidirectional"))
    )
    (net (code "8") (name "ADC_HIGH_CURRENT") (class "Default")
      (node (ref "C2") (pin "1") (pinfunction "1_1") (pintype "passive"))
      (node (ref "D1") (pin "3") (pinfunction "C1A2_3") (pintype "passive"))
      (node (ref "R24") (pin "1") (pinfunction "1_1") (pintype "passive"))
      (node (ref "U$1") (pin "P$24") (pinfunction "PA1/UART4_RX_P$24") (pintype "bidirectional"))
    )
    (net (code "9") (name "ADC_LOW_CURRENT") (class "Default")
      (node (ref "C3") (pin "1") (pinfunction "1_1") (pintype "passive"))
      (node (ref "D2") (pin "3") (pinfunction "C1A2_3") (pintype "passive"))
      (node (ref "R25") (pin "1") (pinfunction "1_1") (pintype "passive"))
      (node (ref "U$1") (pin "P$26") (pinfunction "PA3/USART2_RX_P$26") (pintype "bidirectional"))
    )
    (net (code "10") (name "ADC_PUSHPULL_OUT") (class "Default")
      (node (ref "C47") (pin "1") (pinfunction "1_1") (pintype "passive"))
      (node (ref "D11") (pin "3") (pinfunction "C1A2_3") (pintype "passive"))
      (node (ref "R60") (pin "2") (pinfunction "2_2") (pintype "passive"))
      (node (ref "R67") (pin "1") (pinfunction "1_1") (pintype "passive"))
      (node (ref "U$1") (pin "P$23") (pinfunction "PA0/UART4_TX_P$23") (pintype "bidirectional"))
    )
    (net (code "11") (name "ADC_SUPPLY_HIGHSIDE") (class "Default")
      (node (ref "C46") (pin "1") (pinfunction "1_1") (pintype "passive"))
      (node (ref "R58") (pin "2") (pinfunction "2_2") (pintype "passive"))
      (node (ref "R59") (pin "1") (pinfunction "1_1") (pintype "passive"))
      (node (ref "U$1") (pin "P$17") (pinfunction "PC2/SPI2_MISO_P$17") (pintype "bidirectional"))
    )
    (net (code "12") (name "BATTERY+") (class "Default")
      (node (ref "+") (pin "1@1") (pinfunction "1_1@1") (pintype "bidirectional"))
      (node (ref "+") (pin "1@2") (pinfunction "2_1@2") (pintype "bidirectional"))
      (node (ref "C53") (pin "+") (pinfunction "+_+") (pintype "passive"))
      (node (ref "L6") (pin "2") (pinfunction "2_2") (pintype "passive"))
      (node (ref "R61") (pin "1") (pinfunction "1_1") (pintype "passive"))
    )
    (net (code "13") (name "BIAS_CTRL") (class "Default")
      (node (ref "IC6") (pin "6") (pinfunction "VB_6") (pintype "bidirectional"))
      (node (ref "R28") (pin "2") (pinfunction "2_2") (pintype "passive"))
    )
    (net (code "14") (name "BIAS_CURRENT") (class "Default")
      (node (ref "Q6") (pin "B") (pinfunction "B_B") (pintype "passive"))
      (node (ref "Q7") (pin "B") (pinfunction "B_B") (pintype "passive"))
      (node (ref "Q7") (pin "C") (pinfunction "C_C") (pintype "passive"))
      (node (ref "Q9") (pin "C") (pinfunction "C_C") (pintype "passive"))
    )
    (net (code "15") (name "BUCK_ENABLE") (class "Default")
      (node (ref "IC8") (pin "7") (pinfunction "ON_7") (pintype "passive"))
      (node (ref "R71") (pin "1") (pinfunction "1_1") (pintype "passive"))
    )
    (net (code "16") (name "CURRENT_CTRL") (class "Default")
      (node (ref "IC7") (pin "12") (pinfunction "+IN_12") (pintype "input"))
      (node (ref "R34") (pin "2") (pinfunction "2_2") (pintype "passive"))
      (node (ref "R70") (pin "2") (pinfunction "2_2") (pintype "passive"))
    )
    (net (code "17") (name "CURRENT_SENSE") (class "Default")
      (node (ref "C19") (pin "2") (pinfunction "2_2") (pintype "passive"))
      (node (ref "C20") (pin "2") (pinfunction "2_2") (pintype "passive"))
      (node (ref "IC13") (pin "6") (pinfunction "OUT_6") (pintype "output"))
      (node (ref "R12") (pin "1") (pinfunction "1_1") (pintype "passive"))
      (node (ref "R15") (pin "2") (pinfunction "2_2") (pintype "passive"))
      (node (ref "R19") (pin "2") (pinfunction "2_2") (pintype "passive"))
      (node (ref "R35") (pin "2") (pinfunction "2_2") (pintype "passive"))
      (node (ref "R36") (pin "2") (pinfunction "2_2") (pintype "passive"))
    )
    (net (code "18") (name "DAC_CS") (class "Default")
      (node (ref "IC6") (pin "2") (pinfunction "CS_2") (pintype "bidirectional"))
      (node (ref "U$1") (pin "P$45") (pinfunction "PE14_P$45") (pintype "bidirectional"))
    )
    (net (code "19") (name "DAC_LDAC") (class "Default")
      (node (ref "IC6") (pin "5") (pinfunction "LDAC_5") (pintype "bidirectional"))
      (node (ref "U$1") (pin "P$42") (pinfunction "PE11_P$42") (pintype "bidirectional"))
    )
    (net (code "20") (name "DAC_SCK") (class "Default")
      (node (ref "IC6") (pin "3") (pinfunction "SCK_3") (pintype "bidirectional"))
      (node (ref "U$1") (pin "P$44") (pinfunction "PE13_P$44") (pintype "bidirectional"))
    )
    (net (code "21") (name "DAC_SDI") (class "Default")
      (node (ref "IC6") (pin "4") (pinfunction "SDI_4") (pintype "bidirectional"))
      (node (ref "U$1") (pin "P$43") (pinfunction "PE12_P$43") (pintype "bidirectional"))
    )
    (net (code "22") (name "GND") (class "Default")
      (node (ref "-") (pin "1@1") (pinfunction "1_1@1") (pintype "bidirectional"))
      (node (ref "-") (pin "1@2") (pinfunction "2_1@2") (pintype "bidirectional"))
      (node (ref "C1") (pin "2") (pinfunction "2_2") (pintype "passive"))
      (node (ref "C10") (pin "2") (pinfunction "2_2") (pintype "passive"))
      (node (ref "C11") (pin "2") (pinfunction "2_2") (pintype "passive"))
      (node (ref "C12") (pin "2") (pinfunction "2_2") (pintype "passive"))
      (node (ref "C13") (pin "2") (pinfunction "2_2") (pintype "passive"))
      (node (ref "C14") (pin "2") (pinfunction "2_2") (pintype "passive"))
      (node (ref "C15") (pin "1") (pinfunction "1_1") (pintype "passive"))
      (node (ref "C16") (pin "1") (pinfunction "1_1") (pintype "passive"))
      (node (ref "C2") (pin "2") (pinfunction "2_2") (pintype "passive"))
      (node (ref "C22") (pin "2") (pinfunction "2_2") (pintype "passive"))
      (node (ref "C23") (pin "2") (pinfunction "2_2") (pintype "passive"))
      (node (ref "C24") (pin "-") (pinfunction "-_-") (pintype "passive"))
      (node (ref "C25") (pin "-") (pinfunction "-_-") (pintype "passive"))
      (node (ref "C26") (pin "-") (pinfunction "-_-") (pintype "passive"))
      (node (ref "C27") (pin "2") (pinfunction "2_2") (pintype "passive"))
      (node (ref "C28") (pin "1") (pinfunction "1_1") (pintype "passive"))
      (node (ref "C29") (pin "2") (pinfunction "2_2") (pintype "passive"))
      (node (ref "C3") (pin "2") (pinfunction "2_2") (pintype "passive"))
      (node (ref "C30") (pin "2") (pinfunction "2_2") (pintype "passive"))
      (node (ref "C31") (pin "2") (pinfunction "2_2") (pintype "passive"))
      (node (ref "C32") (pin "2") (pinfunction "2_2") (pintype "passive"))
      (node (ref "C34") (pin "1") (pinfunction "1_1") (pintype "passive"))
      (node (ref "C35") (pin "-") (pinfunction "-_-") (pintype "passive"))
      (node (ref "C36") (pin "1") (pinfunction "1_1") (pintype "passive"))
      (node (ref "C38") (pin "2") (pinfunction "2_2") (pintype "passive"))
      (node (ref "C4") (pin "1") (pinfunction "1_1") (pintype "passive"))
      (node (ref "C40") (pin "+") (pinfunction "+_+") (pintype "passive"))
      (node (ref "C41") (pin "+") (pinfunction "+_+") (pintype "passive"))
      (node (ref "C42") (pin "-") (pinfunction "-_-") (pintype "passive"))
      (node (ref "C46") (pin "2") (pinfunction "2_2") (pintype "passive"))
      (node (ref "C47") (pin "2") (pinfunction "2_2") (pintype "passive"))
      (node (ref "C48") (pin "2") (pinfunction "2_2") (pintype "passive"))
      (node (ref "C49") (pin "2") (pinfunction "2_2") (pintype "passive"))
      (node (ref "C50") (pin "-") (pinfunction "-_-") (pintype "passive"))
      (node (ref "C51") (pin "2") (pinfunction "2_2") (pintype "passive"))
      (node (ref "C52") (pin "1") (pinfunction "1_1") (pintype "passive"))
      (node (ref "C53") (pin "-") (pinfunction "-_-") (pintype "passive"))
      (node (ref "C54") (pin "2") (pinfunction "2_2") (pintype "passive"))
      (node (ref "C7") (pin "2") (pinfunction "2_2") (pintype "passive"))
      (node (ref "C8") (pin "2") (pinfunction "2_2") (pintype "passive"))
      (node (ref "C9") (pin "2") (pinfunction "2_2") (pintype "passive"))
      (node (ref "D1") (pin "1") (pinfunction "A1_1") (pintype "passive"))
      (node (ref "D10") (pin "A") (pinfunction "A_A") (pintype "passive"))
      (node (ref "D11") (pin "1") (pinfunction "A1_1") (pintype "passive"))
      (node (ref "D12") (pin "1") (pinfunction "A1_1") (pintype "passive"))
      (node (ref "D13") (pin "2") (pinfunction "COM_2") (pintype "bidirectional"))
      (node (ref "D2") (pin "1") (pinfunction "A1_1") (pintype "passive"))
      (node (ref "D6") (pin "A") (pinfunction "A_A") (pintype "passive"))
      (node (ref "D7") (pin "1") (pinfunction "A1_1") (pintype "passive"))
      (node (ref "D8") (pin "C") (pinfunction "C_C") (pintype "passive"))
      (node (ref "D9") (pin "1") (pinfunction "A1_1") (pintype "passive"))
      (node (ref "DISPLAY") (pin "1") (pinfunction "GND_1") (pintype "bidirectional"))
      (node (ref "IC11") (pin "3") (pinfunction "+IN_3") (pintype "input"))
      (node (ref "IC11") (pin "5") (pinfunction "+IN_5") (pintype "input"))
      (node (ref "IC12") (pin "3") (pinfunction "INH_3") (pintype "input"))
      (node (ref "IC12") (pin "7") (pinfunction "GND_7") (pintype "power_in"))
      (node (ref "IC12") (pin "EXP") (pinfunction "EXP_EXP") (pintype "input"))
      (node (ref "IC14") (pin "1") (pinfunction "GND_1") (pintype "input"))
      (node (ref "IC4") (pin "2") (pinfunction "A_2") (pintype "passive"))
      (node (ref "IC4") (pin "3") (pinfunction "A_3") (pintype "passive"))
      (node (ref "IC4") (pin "6") (pinfunction "A_6") (pintype "passive"))
      (node (ref "IC4") (pin "7") (pinfunction "A_7") (pintype "passive"))
      (node (ref "IC6") (pin "7") (pinfunction "VSS_7") (pintype "bidirectional"))
      (node (ref "IC7") (pin "5") (pinfunction "+IN_5") (pintype "input"))
      (node (ref "IC8") (pin "4") (pinfunction "GND_4") (pintype "power_in"))
      (node (ref "IC9") (pin "2") (pinfunction "GND_2") (pintype "power_in"))
      (node (ref "LED1") (pin "C") (pinfunction "C_C") (pintype "passive"))
      (node (ref "LED2") (pin "C") (pinfunction "C_C") (pintype "passive"))
      (node (ref "PAD2") (pin "1") (pinfunction "P_1") (pintype "passive"))
      (node (ref "Q11") (pin "E") (pinfunction "E_E") (pintype "passive"))
      (node (ref "Q12") (pin "E") (pinfunction "E_E") (pintype "passive"))
      (node (ref "Q13") (pin "E") (pinfunction "E_E") (pintype "passive"))
      (node (ref "Q15") (pin "2") (pinfunction "S_2") (pintype "passive"))
      (node (ref "R13") (pin "1") (pinfunction "1_1") (pintype "passive"))
      (node (ref "R17") (pin "2") (pinfunction "2_2") (pintype "passive"))
      (node (ref "R21") (pin "2") (pinfunction "2_2") (pintype "passive"))
      (node (ref "R44") (pin "1") (pinfunction "1_1") (pintype "passive"))
      (node (ref "R45") (pin "1") (pinfunction "1_1") (pintype "passive"))
      (node (ref "R47") (pin "2") (pinfunction "2_2") (pintype "passive"))
      (node (ref "R48") (pin "1") (pinfunction "1_1") (pintype "passive"))
      (node (ref "R50") (pin "1") (pinfunction "1_1") (pintype "passive"))
      (node (ref "R53") (pin "1") (pinfunction "1_1") (pintype "passive"))
      (node (ref "R54") (pin "1") (pinfunction "1_1") (pintype "passive"))
      (node (ref "R55") (pin "1") (pinfunction "1_1") (pintype "passive"))
      (node (ref "R59") (pin "2") (pinfunction "2_2") (pintype "passive"))
      (node (ref "R62") (pin "2") (pinfunction "2_2") (pintype "passive"))
      (node (ref "R67") (pin "2") (pinfunction "2_2") (pintype "passive"))
      (node (ref "S1") (pin "2") (pinfunction "S_2") (pintype "passive"))
      (node (ref "SWDIO") (pin "3") (pinfunction "3_3") (pintype "passive"))
      (node (ref "U$1") (pin "P$10") (pinfunction "VSS1_P$10") (pintype "bidirectional"))
      (node (ref "U$1") (pin "P$20") (pinfunction "VSSA_P$20") (pintype "bidirectional"))
      (node (ref "U$1") (pin "P$27") (pinfunction "VSS2_P$27") (pintype "bidirectional"))
      (node (ref "U$1") (pin "P$74") (pinfunction "VSS3_P$74") (pintype "bidirectional"))
      (node (ref "U$1") (pin "P$94") (pinfunction "BOOT0_P$94") (pintype "bidirectional"))
      (node (ref "U$1") (pin "P$99") (pinfunction "VSS4_P$99") (pintype "bidirectional"))
      (node (ref "UART") (pin "1") (pinfunction "1_1") (pintype "passive"))
      (node (ref "X1") (pin "5") (pinfunction "5_5") (pintype "passive"))
      (node (ref "X1") (pin "M1") (pinfunction "S1_M1") (pintype "passive"))
      (node (ref "X1") (pin "M2") (pinfunction "S2_M2") (pintype "passive"))
      (node (ref "X1") (pin "M3") (pinfunction "S3_M3") (pintype "passive"))
      (node (ref "X1") (pin "M4") (pinfunction "S4_M4") (pintype "passive"))
    )
    (net (code "23") (name "HIGHSIDE_SUPPLY_CTRL") (class "Default")
      (node (ref "IC6") (pin "8") (pinfunction "VA_8") (pintype "bidirectional"))
      (node (ref "R43") (pin "1") (pinfunction "1_1") (pintype "passive"))
    )
    (net (code "24") (name "LCD_CLK") (class "Default")
      (node (ref "DISPLAY") (pin "18") (pinfunction "CLK_18") (pintype "bidirectional"))
      (node (ref "DISPLAY") (pin "32") (pinfunction "CLK_32") (pintype "bidirectional"))
      (node (ref "U$1") (pin "P$78") (pinfunction "PC10/SPI3_SCK/USART3_TX/UART4_TX_P$78") (pintype "bidirectional"))
    )
    (net (code "25") (name "LCD_CS") (class "Default")
      (node (ref "DISPLAY") (pin "29") (pinfunction "CS_29") (pintype "bidirectional"))
      (node (ref "U$1") (pin "P$95") (pinfunction "PB8/I2C1_SCL/CAN1_RX_P$95") (pintype "bidirectional"))
    )
    (net (code "26") (name "LCD_MISO") (class "Default")
      (node (ref "DISPLAY") (pin "26") (pinfunction "DOUT_26") (pintype "bidirectional"))
      (node (ref "DISPLAY") (pin "30") (pinfunction "MISO_30") (pintype "bidirectional"))
      (node (ref "U$1") (pin "P$79") (pinfunction "PC11/SPI3_MISO/USART3_RX/UART4_RX_P$79") (pintype "bidirectional"))
    )
    (net (code "27") (name "LCD_MOSI") (class "Default")
      (node (ref "DISPLAY") (pin "22") (pinfunction "DIN_22") (pintype "bidirectional"))
      (node (ref "DISPLAY") (pin "34") (pinfunction "MOSI_34") (pintype "bidirectional"))
      (node (ref "U$1") (pin "P$80") (pinfunction "PC12/SPI3_MOSI/UART5_TX_P$80") (pintype "bidirectional"))
    )
    (net (code "28") (name "LCD_RD") (class "Default")
      (node (ref "DISPLAY") (pin "11") (pinfunction "RD_11") (pintype "bidirectional"))
      (node (ref "U$1") (pin "P$66") (pinfunction "PC9/I2C3_SDA_P$66") (pintype "bidirectional"))
    )
    (net (code "29") (name "LCD_RESET") (class "Default")
      (node (ref "DISPLAY") (pin "33") (pinfunction "RST_33") (pintype "bidirectional"))
      (node (ref "U$1") (pin "P$96") (pinfunction "PB9/I2C1_SDA/CAN1_TX_P$96") (pintype "bidirectional"))
    )
    (net (code "30") (name "LCD_RS") (class "Default")
      (node (ref "DISPLAY") (pin "7") (pinfunction "RS_7") (pintype "bidirectional"))
      (node (ref "U$1") (pin "P$64") (pinfunction "PC7/USART6_RX_P$64") (pintype "bidirectional"))
    )
    (net (code "31") (name "LCD_SD_CS") (class "Default")
      (node (ref "DISPLAY") (pin "36") (pinfunction "CS_36") (pintype "bidirectional"))
      (node (ref "U$1") (pin "P$97") (pinfunction "PE0_P$97") (pintype "bidirectional"))
    )
    (net (code "32") (name "LCD_TOUCH_BUSY") (class "Default")
      (node (ref "DISPLAY") (pin "24") (pinfunction "BUSY_24") (pintype "bidirectional"))
      (node (ref "U$1") (pin "P$90") (pinfunction "PB4/SPI1_MISO/SPI3_MISO_P$90") (pintype "bidirectional"))
    )
    (net (code "33") (name "LCD_TOUCH_CS") (class "Default")
      (node (ref "DISPLAY") (pin "20") (pinfunction "CS_20") (pintype "bidirectional"))
      (node (ref "U$1") (pin "P$89") (pinfunction "PB3/SPI1_SCK/SPI3_SCK_P$89") (pintype "bidirectional"))
    )
    (net (code "34") (name "LCD_TOUCH_IRQ") (class "Default")
      (node (ref "DISPLAY") (pin "28") (pinfunction "IRQ_28") (pintype "bidirectional"))
      (node (ref "U$1") (pin "P$91") (pinfunction "PB5/SPI1_MOSI/SPI3_MOSI/CAN2_RX_P$91") (pintype "bidirectional"))
    )
    (net (code "35") (name "LCD_WR") (class "Default")
      (node (ref "DISPLAY") (pin "9") (pinfunction "WR_9") (pintype "bidirectional"))
      (node (ref "U$1") (pin "P$65") (pinfunction "PC8_P$65") (pintype "bidirectional"))
    )
    (net (code "36") (name "LED1") (class "Default")
      (node (ref "R63") (pin "1") (pinfunction "1_1") (pintype "passive"))
      (node (ref "U$1") (pin "P$2") (pinfunction "PE3_P$2") (pintype "bidirectional"))
    )
    (net (code "37") (name "LED2") (class "Default")
      (node (ref "R65") (pin "1") (pinfunction "1_1") (pintype "passive"))
      (node (ref "U$1") (pin "P$3") (pinfunction "PE4_P$3") (pintype "bidirectional"))
    )
    (net (code "38") (name "NRST") (class "Default")
      (node (ref "C14") (pin "1") (pinfunction "1_1") (pintype "passive"))
      (node (ref "R32") (pin "1") (pinfunction "1_1") (pintype "passive"))
      (node (ref "SWDIO") (pin "1") (pinfunction "1_1") (pintype "passive"))
      (node (ref "U$1") (pin "P$14") (pinfunction "NRST_P$14") (pintype "bidirectional"))
    )
    (net (code "39") (name "Net-(C33-Pad2)") (class "Default")
      (node (ref "C33") (pin "2") (pinfunction "2_2") (pintype "passive"))
      (node (ref "R54") (pin "2") (pinfunction "2_2") (pintype "passive"))
    )
    (net (code "40") (name "Net-(C37-Pad1)") (class "Default")
      (node (ref "C37") (pin "1") (pinfunction "1_1") (pintype "passive"))
      (node (ref "D8") (pin "A") (pinfunction "A_A") (pintype "passive"))
      (node (ref "L5") (pin "1") (pinfunction "1_1") (pintype "passive"))
    )
    (net (code "41") (name "Net-(C38-Pad1)") (class "Default")
      (node (ref "C38") (pin "1") (pinfunction "1_1") (pintype "passive"))
      (node (ref "R55") (pin "2") (pinfunction "2_2") (pintype "passive"))
      (node (ref "R56") (pin "1") (pinfunction "1_1") (pintype "passive"))
    )
    (net (code "42") (name "Net-(C39-Pad1)") (class "Default")
      (node (ref "C39") (pin "1") (pinfunction "1_1") (pintype "passive"))
      (node (ref "C40") (pin "-") (pinfunction "-_-") (pintype "passive"))
      (node (ref "L5") (pin "2") (pinfunction "2_2") (pintype "passive"))
      (node (ref "L8") (pin "1") (pinfunction "1_1") (pintype "passive"))
      (node (ref "R57") (pin "2") (pinfunction "2_2") (pintype "passive"))
    )
    (net (code "43") (name "Net-(C52-Pad2)") (class "Default")
      (node (ref "C52") (pin "2") (pinfunction "2_2") (pintype "passive"))
      (node (ref "R37") (pin "1") (pinfunction "1_1") (pintype "passive"))
      (node (ref "R68") (pin "2") (pinfunction "2_2") (pintype "passive"))
    )
    (net (code "44") (name "Net-(D3-A)") (class "Default")
      (node (ref "D3") (pin "2") (pinfunction "A_2") (pintype "passive"))
      (node (ref "D5") (pin "2") (pinfunction "A_2") (pintype "passive"))
      (node (ref "Q5") (pin "B") (pinfunction "B_B") (pintype "passive"))
      (node (ref "Q8") (pin "B") (pinfunction "B_B") (pintype "passive"))
      (node (ref "Q8") (pin "C") (pinfunction "C_C") (pintype "passive"))
    )
    (net (code "45") (name "Net-(D3-C)") (class "Default")
      (node (ref "D3") (pin "1") (pinfunction "C_1") (pintype "passive"))
      (node (ref "Q14") (pin "E") (pinfunction "E_E") (pintype "passive"))
    )
    (net (code "46") (name "Net-(D4-A)") (class "Default")
      (node (ref "D4") (pin "2") (pinfunction "A_2") (pintype "passive"))
      (node (ref "K1") (pin "2") (pinfunction "2_2") (pintype "passive"))
      (node (ref "Q13") (pin "C") (pinfunction "C_C") (pintype "passive"))
    )
    (net (code "47") (name "Net-(D5-C)") (class "Default")
      (node (ref "C18") (pin "2") (pinfunction "2_2") (pintype "passive"))
      (node (ref "D5") (pin "1") (pinfunction "C_1") (pintype "passive"))
      (node (ref "IC7") (pin "14") (pinfunction "OUT_14") (pintype "output"))
    )
    (net (code "48") (name "Net-(D9-C1A2)") (class "Default")
      (node (ref "D9") (pin "3") (pinfunction "C1A2_3") (pintype "passive"))
      (node (ref "IC8") (pin "6") (pinfunction "FB_6") (pintype "input"))
      (node (ref "R37") (pin "2") (pinfunction "2_2") (pintype "passive"))
      (node (ref "R38") (pin "1") (pinfunction "1_1") (pintype "passive"))
    )
    (net (code "49") (name "Net-(D13-2)") (class "Default")
      (node (ref "D13") (pin "3") (pinfunction "2_3") (pintype "bidirectional"))
      (node (ref "R97") (pin "1") (pinfunction "1_1") (pintype "passive"))
      (node (ref "X1") (pin "3") (pinfunction "3_3") (pintype "passive"))
    )
    (net (code "50") (name "Net-(D13-3)") (class "Default")
      (node (ref "D13") (pin "4") (pinfunction "3_4") (pintype "bidirectional"))
      (node (ref "R98") (pin "1") (pinfunction "1_1") (pintype "passive"))
      (node (ref "X1") (pin "1") (pinfunction "1_1") (pintype "passive"))
    )
    (net (code "51") (name "Net-(D13-4)") (class "Default")
      (node (ref "D13") (pin "5") (pinfunction "4_5") (pintype "bidirectional"))
      (node (ref "R64") (pin "1") (pinfunction "1_1") (pintype "passive"))
      (node (ref "X1") (pin "2") (pinfunction "2_2") (pintype "passive"))
    )
    (net (code "52") (name "Net-(D13-Pad1)") (class "Default")
      (node (ref "D13") (pin "1") (pinfunction "1_1") (pintype "bidirectional"))
      (node (ref "R100") (pin "1") (pinfunction "1_1") (pintype "passive"))
      (node (ref "X1") (pin "4") (pinfunction "4_4") (pintype "passive"))
    )
    (net (code "53") (name "Net-(DISPLAYC-DB0)") (class "Default")
      (node (ref "DISPLAY") (pin "2") (pinfunction "DB0_2") (pintype "bidirectional"))
      (node (ref "U$1") (pin "P$55") (pinfunction "PD8/USART3_TX_P$55") (pintype "bidirectional"))
    )
    (net (code "54") (name "Net-(DISPLAYC-DB1)") (class "Default")
      (node (ref "DISPLAY") (pin "4") (pinfunction "DB1_4") (pintype "bidirectional"))
      (node (ref "U$1") (pin "P$56") (pinfunction "PD9/USART3_RX_P$56") (pintype "bidirectional"))
    )
    (net (code "55") (name "Net-(DISPLAYC-DB2)") (class "Default")
      (node (ref "DISPLAY") (pin "6") (pinfunction "DB2_6") (pintype "bidirectional"))
      (node (ref "U$1") (pin "P$57") (pinfunction "PD10_P$57") (pintype "bidirectional"))
    )
    (net (code "56") (name "Net-(DISPLAYC-DB3)") (class "Default")
      (node (ref "DISPLAY") (pin "8") (pinfunction "DB3_8") (pintype "bidirectional"))
      (node (ref "U$1") (pin "P$58") (pinfunction "PD11_P$58") (pintype "bidirectional"))
    )
    (net (code "57") (name "Net-(DISPLAYC-DB4)") (class "Default")
      (node (ref "DISPLAY") (pin "10") (pinfunction "DB4_10") (pintype "bidirectional"))
      (node (ref "U$1") (pin "P$59") (pinfunction "PD12_P$59") (pintype "bidirectional"))
    )
    (net (code "58") (name "Net-(DISPLAYC-DB5)") (class "Default")
      (node (ref "DISPLAY") (pin "12") (pinfunction "DB5_12") (pintype "bidirectional"))
      (node (ref "U$1") (pin "P$60") (pinfunction "PD13_P$60") (pintype "bidirectional"))
    )
    (net (code "59") (name "Net-(DISPLAYC-DB6)") (class "Default")
      (node (ref "DISPLAY") (pin "14") (pinfunction "DB6_14") (pintype "bidirectional"))
      (node (ref "U$1") (pin "P$61") (pinfunction "PD14_P$61") (pintype "bidirectional"))
    )
    (net (code "60") (name "Net-(DISPLAYC-DB7)") (class "Default")
      (node (ref "DISPLAY") (pin "16") (pinfunction "DB7_16") (pintype "bidirectional"))
      (node (ref "U$1") (pin "P$62") (pinfunction "PD15_P$62") (pintype "bidirectional"))
    )
    (net (code "61") (name "Net-(DISPLAYC-DB8)") (class "Default")
      (node (ref "DISPLAY") (pin "13") (pinfunction "DB8_13") (pintype "bidirectional"))
      (node (ref "U$1") (pin "P$81") (pinfunction "PD0/CAN1_RX_P$81") (pintype "bidirectional"))
    )
    (net (code "62") (name "Net-(DISPLAYC-DB9)") (class "Default")
      (node (ref "DISPLAY") (pin "15") (pinfunction "DB9_15") (pintype "bidirectional"))
      (node (ref "U$1") (pin "P$82") (pinfunction "PD1/CAN1_TX_P$82") (pintype "bidirectional"))
    )
    (net (code "63") (name "Net-(DISPLAYC-DB10)") (class "Default")
      (node (ref "DISPLAY") (pin "17") (pinfunction "DB10_17") (pintype "bidirectional"))
      (node (ref "U$1") (pin "P$83") (pinfunction "PD2/UART5_RX_P$83") (pintype "bidirectional"))
    )
    (net (code "64") (name "Net-(DISPLAYC-DB11)") (class "Default")
      (node (ref "DISPLAY") (pin "19") (pinfunction "DB11_19") (pintype "bidirectional"))
      (node (ref "U$1") (pin "P$84") (pinfunction "PD3_P$84") (pintype "bidirectional"))
    )
    (net (code "65") (name "Net-(DISPLAYC-DB12)") (class "Default")
      (node (ref "DISPLAY") (pin "21") (pinfunction "DB12_21") (pintype "bidirectional"))
      (node (ref "U$1") (pin "P$85") (pinfunction "PD4_P$85") (pintype "bidirectional"))
    )
    (net (code "66") (name "Net-(DISPLAYC-DB13)") (class "Default")
      (node (ref "DISPLAY") (pin "23") (pinfunction "DB13_23") (pintype "bidirectional"))
      (node (ref "U$1") (pin "P$86") (pinfunction "PD5/USART2_TX_P$86") (pintype "bidirectional"))
    )
    (net (code "67") (name "Net-(DISPLAYC-DB14)") (class "Default")
      (node (ref "DISPLAY") (pin "25") (pinfunction "DB14_25") (pintype "bidirectional"))
      (node (ref "U$1") (pin "P$87") (pinfunction "PD6/USART2_RX_P$87") (pintype "bidirectional"))
    )
    (net (code "68") (name "Net-(DISPLAYC-DB15)") (class "Default")
      (node (ref "DISPLAY") (pin "27") (pinfunction "DB15_27") (pintype "bidirectional"))
      (node (ref "U$1") (pin "P$88") (pinfunction "PD7_P$88") (pintype "bidirectional"))
    )
    (net (code "69") (name "Net-(DISPLAYD-LED_A+)") (class "Default")
      (node (ref "DISPLAY") (pin "37") (pinfunction "LED_A+_37") (pintype "bidirectional"))
      (node (ref "R66") (pin "2") (pinfunction "2_2") (pintype "passive"))
    )
    (net (code "70") (name "Net-(IC1-+IN)") (class "Default")
      (node (ref "IC1") (pin "3") (pinfunction "+IN_3") (pintype "input"))
      (node (ref "R18") (pin "1") (pinfunction "1_1") (pintype "passive"))
      (node (ref "R21") (pin "1") (pinfunction "1_1") (pintype "passive"))
    )
    (net (code "71") (name "Net-(IC1--IN)") (class "Default")
      (node (ref "IC1") (pin "2") (pinfunction "-IN_2") (pintype "input"))
      (node (ref "R19") (pin "1") (pinfunction "1_1") (pintype "passive"))
      (node (ref "R20") (pin "2") (pinfunction "2_2") (pintype "passive"))
    )
    (net (code "72") (name "Net-(IC1-OUT)") (class "Default")
      (node (ref "IC1") (pin "6") (pinfunction "OUT_6") (pintype "output"))
      (node (ref "R20") (pin "1") (pinfunction "1_1") (pintype "passive"))
      (node (ref "R25") (pin "2") (pinfunction "2_2") (pintype "passive"))
    )
    (net (code "73") (name "Net-(IC2-+IN)") (class "Default")
      (node (ref "IC2") (pin "3") (pinfunction "+IN_3") (pintype "input"))
      (node (ref "R14") (pin "1") (pinfunction "1_1") (pintype "passive"))
      (node (ref "R17") (pin "1") (pinfunction "1_1") (pintype "passive"))
    )
    (net (code "74") (name "Net-(IC2--IN)") (class "Default")
      (node (ref "IC2") (pin "2") (pinfunction "-IN_2") (pintype "input"))
      (node (ref "R15") (pin "1") (pinfunction "1_1") (pintype "passive"))
      (node (ref "R16") (pin "2") (pinfunction "2_2") (pintype "passive"))
    )
    (net (code "75") (name "Net-(IC2-OUT)") (class "Default")
      (node (ref "IC2") (pin "6") (pinfunction "OUT_6") (pintype "output"))
      (node (ref "R16") (pin "1") (pinfunction "1_1") (pintype "passive"))
      (node (ref "R24") (pin "2") (pinfunction "2_2") (pintype "passive"))
    )
    (net (code "76") (name "Net-(IC4-C)") (class "Default")
      (node (ref "C54") (pin "1") (pinfunction "1_1") (pintype "passive"))
      (node (ref "IC4") (pin "1") (pinfunction "C_1") (pintype "passive"))
      (node (ref "IC4") (pin "8") (pinfunction "R_8") (pintype "passive"))
      (node (ref "R22") (pin "2") (pinfunction "2_2") (pintype "passive"))
      (node (ref "R23") (pin "1") (pinfunction "1_1") (pintype "passive"))
    )
    (net (code "77") (name "Net-(IC5-+IN)") (class "Default")
      (node (ref "C1") (pin "1") (pinfunction "1_1") (pintype "passive"))
      (node (ref "IC5") (pin "3") (pinfunction "+IN_3") (pintype "input"))
      (node (ref "R23") (pin "2") (pinfunction "2_2") (pintype "passive"))
    )
    (net (code "78") (name "Net-(IC7A-+IN)") (class "Default")
      (node (ref "IC7") (pin "3") (pinfunction "+IN_3") (pintype "input"))
      (node (ref "IC7") (pin "7") (pinfunction "OUT_7") (pintype "output"))
      (node (ref "R33") (pin "1") (pinfunction "1_1") (pintype "passive"))
    )
    (net (code "79") (name "Net-(IC7A--IN)") (class "Default")
      (node (ref "C17") (pin "1") (pinfunction "1_1") (pintype "passive"))
      (node (ref "C20") (pin "1") (pinfunction "1_1") (pintype "passive"))
      (node (ref "IC7") (pin "2") (pinfunction "-IN_2") (pintype "input"))
      (node (ref "R36") (pin "1") (pinfunction "1_1") (pintype "passive"))
      (node (ref "R50") (pin "2") (pinfunction "2_2") (pintype "passive"))
    )
    (net (code "80") (name "Net-(IC7A-OUT)") (class "Default")
      (node (ref "C17") (pin "2") (pinfunction "2_2") (pintype "passive"))
      (node (ref "IC7") (pin "1") (pinfunction "OUT_1") (pintype "output"))
      (node (ref "Q14") (pin "C") (pinfunction "C_C") (pintype "passive"))
    )
    (net (code "81") (name "Net-(IC7B--IN)") (class "Default")
      (node (ref "IC7") (pin "6") (pinfunction "-IN_6") (pintype "input"))
      (node (ref "R33") (pin "2") (pinfunction "2_2") (pintype "passive"))
      (node (ref "R34") (pin "1") (pinfunction "1_1") (pintype "passive"))
    )
    (net (code "82") (name "Net-(IC7C--IN)") (class "Default")
      (node (ref "C5") (pin "1") (pinfunction "1_1") (pintype "passive"))
      (node (ref "C6") (pin "1") (pinfunction "1_1") (pintype "passive"))
      (node (ref "IC7") (pin "9") (pinfunction "-IN_9") (pintype "input"))
      (node (ref "R29") (pin "1") (pinfunction "1_1") (pintype "passive"))
      (node (ref "R30") (pin "2") (pinfunction "2_2") (pintype "passive"))
      (node (ref "R44") (pin "2") (pinfunction "2_2") (pintype "passive"))
    )
    (net (code "83") (name "Net-(IC7C-OUT)") (class "Default")
      (node (ref "C5") (pin "2") (pinfunction "2_2") (pintype "passive"))
      (node (ref "IC7") (pin "8") (pinfunction "OUT_8") (pintype "output"))
      (node (ref "Q14") (pin "B") (pinfunction "B_B") (pintype "passive"))
    )
    (net (code "84") (name "Net-(IC7D--IN)") (class "Default")
      (node (ref "C18") (pin "1") (pinfunction "1_1") (pintype "passive"))
      (node (ref "C19") (pin "1") (pinfunction "1_1") (pintype "passive"))
      (node (ref "IC7") (pin "13") (pinfunction "-IN_13") (pintype "input"))
      (node (ref "R35") (pin "1") (pinfunction "1_1") (pintype "passive"))
      (node (ref "R48") (pin "2") (pinfunction "2_2") (pintype "passive"))
    )
    (net (code "85") (name "Net-(IC8-CB)") (class "Default")
      (node (ref "C21") (pin "1") (pinfunction "1_1") (pintype "passive"))
      (node (ref "IC8") (pin "3") (pinfunction "CB_3") (pintype "input"))
    )
    (net (code "86") (name "Net-(IC8-VSW)") (class "Default")
      (node (ref "C21") (pin "2") (pinfunction "2_2") (pintype "passive"))
      (node (ref "D6") (pin "C") (pinfunction "C_C") (pintype "passive"))
      (node (ref "IC8") (pin "1") (pinfunction "VSW_1") (pintype "output"))
      (node (ref "L1") (pin "1") (pinfunction "1_1") (pintype "passive"))
    )
    (net (code "87") (name "Net-(IC9-NFB)") (class "Default")
      (node (ref "C39") (pin "2") (pinfunction "2_2") (pintype "passive"))
      (node (ref "IC9") (pin "3") (pinfunction "NFB_3") (pintype "input"))
      (node (ref "R56") (pin "2") (pinfunction "2_2") (pintype "passive"))
      (node (ref "R57") (pin "1") (pinfunction "1_1") (pintype "passive"))
    )
    (net (code "88") (name "Net-(IC9-SW)") (class "Default")
      (node (ref "C37") (pin "2") (pinfunction "2_2") (pintype "passive"))
      (node (ref "IC9") (pin "1") (pinfunction "SW_1") (pintype "output"))
      (node (ref "L4") (pin "2") (pinfunction "2_2") (pintype "passive"))
    )
    (net (code "89") (name "Net-(IC10--IN)") (class "Default")
      (node (ref "IC10") (pin "2") (pinfunction "-IN_2") (pintype "input"))
      (node (ref "R46") (pin "2") (pinfunction "2_2") (pintype "passive"))
      (node (ref "R47") (pin "1") (pinfunction "1_1") (pintype "passive"))
    )
    (net (code "90") (name "Net-(IC10-OUT)") (class "Default")
      (node (ref "IC10") (pin "6") (pinfunction "OUT_6") (pintype "output"))
      (node (ref "R46") (pin "1") (pinfunction "1_1") (pintype "passive"))
      (node (ref "R49") (pin "2") (pinfunction "2_2") (pintype "passive"))
    )
    (net (code "91") (name "Net-(IC11A--IN)") (class "Default")
      (node (ref "IC11") (pin "2") (pinfunction "-IN_2") (pintype "input"))
      (node (ref "R42") (pin "1") (pinfunction "1_1") (pintype "passive"))
      (node (ref "R43") (pin "2") (pinfunction "2_2") (pintype "passive"))
    )
    (net (code "92") (name "Net-(IC11A-OUT)") (class "Default")
      (node (ref "IC11") (pin "1") (pinfunction "OUT_1") (pintype "output"))
      (node (ref "R41") (pin "1") (pinfunction "1_1") (pintype "passive"))
      (node (ref "R42") (pin "2") (pinfunction "2_2") (pintype "passive"))
    )
    (net (code "93") (name "Net-(IC11B--IN)") (class "Default")
      (node (ref "IC11") (pin "6") (pinfunction "-IN_6") (pintype "input"))
      (node (ref "R39") (pin "1") (pinfunction "1_1") (pintype "passive"))
      (node (ref "R40") (pin "2") (pinfunction "2_2") (pintype "passive"))
      (node (ref "R41") (pin "2") (pinfunction "2_2") (pintype "passive"))
    )
    (net (code "94") (name "Net-(IC11B-OUT)") (class "Default")
      (node (ref "IC11") (pin "7") (pinfunction "OUT_7") (pintype "output"))
      (node (ref "R39") (pin "2") (pinfunction "2_2") (pintype "passive"))
      (node (ref "R68") (pin "1") (pinfunction "1_1") (pintype "passive"))
    )
    (net (code "95") (name "Net-(IC12B-COMP)") (class "Default")
      (node (ref "C32") (pin "1") (pinfunction "1_1") (pintype "passive"))
      (node (ref "C33") (pin "1") (pinfunction "1_1") (pintype "passive"))
      (node (ref "IC12") (pin "4") (pinfunction "COMP_4") (pintype "passive"))
    )
    (net (code "96") (name "Net-(IC12B-FB)") (class "Default")
      (node (ref "IC12") (pin "5") (pinfunction "FB_5") (pintype "input"))
      (node (ref "R52") (pin "1") (pinfunction "1_1") (pintype "passive"))
      (node (ref "R53") (pin "2") (pinfunction "2_2") (pintype "passive"))
    )
    (net (code "97") (name "Net-(IC12B-OUT)") (class "Default")
      (node (ref "D10") (pin "C") (pinfunction "C_C") (pintype "passive"))
      (node (ref "IC12") (pin "1") (pinfunction "OUT_1") (pintype "output"))
      (node (ref "L3") (pin "1") (pinfunction "1_1") (pintype "passive"))
    )
    (net (code "98") (name "Net-(IC13A-IN+)") (class "Default")
      (node (ref "IC13") (pin "3") (pinfunction "IN+_3") (pintype "input"))
      (node (ref "R10") (pin "1") (pinfunction "1_1") (pintype "passive"))
      (node (ref "R13") (pin "2") (pinfunction "2_2") (pintype "passive"))
    )
    (net (code "99") (name "Net-(IC13A-IN-)") (class "Default")
      (node (ref "IC13") (pin "2") (pinfunction "IN-_2") (pintype "input"))
      (node (ref "R11") (pin "1") (pinfunction "1_1") (pintype "passive"))
      (node (ref "R12") (pin "2") (pinfunction "2_2") (pintype "passive"))
    )
    (net (code "100") (name "Net-(K1-PadS)") (class "Default")
      (node (ref "K1") (pin "S") (pinfunction "S_S") (pintype "passive"))
      (node (ref "L6") (pin "1") (pinfunction "1_1") (pintype "passive"))
    )
    (net (code "101") (name "Net-(LED1-PadA)") (class "Default")
      (node (ref "LED1") (pin "A") (pinfunction "A_A") (pintype "passive"))
      (node (ref "R63") (pin "2") (pinfunction "2_2") (pintype "passive"))
    )
    (net (code "102") (name "Net-(LED2-PadA)") (class "Default")
      (node (ref "LED2") (pin "A") (pinfunction "A_A") (pintype "passive"))
      (node (ref "R65") (pin "2") (pinfunction "2_2") (pintype "passive"))
    )
    (net (code "103") (name "Net-(Q1-PadB)") (class "Default")
      (node (ref "Q1") (pin "B") (pinfunction "B_B") (pintype "passive"))
      (node (ref "Q3") (pin "C") (pinfunction "C_C") (pintype "passive"))
      (node (ref "R5") (pin "1") (pinfunction "1_1") (pintype "passive"))
    )
    (net (code "104") (name "Net-(Q1-PadE)") (class "Default")
      (node (ref "Q1") (pin "E") (pinfunction "E_E") (pintype "passive"))
      (node (ref "Q5") (pin "E") (pinfunction "E_E") (pintype "passive"))
      (node (ref "R4") (pin "1") (pinfunction "1_1") (pintype "passive"))
      (node (ref "R5") (pin "2") (pinfunction "2_2") (pintype "passive"))
    )
    (net (code "105") (name "Net-(Q2-PadB)") (class "Default")
      (node (ref "Q2") (pin "B") (pinfunction "B_B") (pintype "passive"))
      (node (ref "Q4") (pin "C") (pinfunction "C_C") (pintype "passive"))
      (node (ref "R1") (pin "2") (pinfunction "2_2") (pintype "passive"))
    )
    (net (code "106") (name "Net-(Q3-PadB)") (class "Default")
      (node (ref "Q3") (pin "B") (pinfunction "B_B") (pintype "passive"))
      (node (ref "Q5") (pin "C") (pinfunction "C_C") (pintype "passive"))
      (node (ref "R6") (pin "1") (pinfunction "1_1") (pintype "passive"))
    )
    (net (code "107") (name "Net-(Q4-PadB)") (class "Default")
      (node (ref "Q4") (pin "B") (pinfunction "B_B") (pintype "passive"))
      (node (ref "Q6") (pin "C") (pinfunction "C_C") (pintype "passive"))
      (node (ref "R2") (pin "1") (pinfunction "1_1") (pintype "passive"))
    )
    (net (code "108") (name "Net-(Q7-PadE)") (class "Default")
      (node (ref "Q7") (pin "E") (pinfunction "E_E") (pintype "passive"))
      (node (ref "Q8") (pin "E") (pinfunction "E_E") (pintype "passive"))
    )
    (net (code "109") (name "Net-(Q9-PadE)") (class "Default")
      (node (ref "Q9") (pin "E") (pinfunction "E_E") (pintype "passive"))
      (node (ref "R27") (pin "1") (pinfunction "1_1") (pintype "passive"))
    )
    (net (code "110") (name "Net-(Q10-PadB)") (class "Default")
      (node (ref "Q10") (pin "B") (pinfunction "B_B") (pintype "passive"))
      (node (ref "Q10") (pin "C") (pinfunction "C_C") (pintype "passive"))
      (node (ref "Q11") (pin "C") (pinfunction "C_C") (pintype "passive"))
      (node (ref "Q9") (pin "B") (pinfunction "B_B") (pintype "passive"))
    )
    (net (code "111") (name "Net-(Q10-PadE)") (class "Default")
      (node (ref "Q10") (pin "E") (pinfunction "E_E") (pintype "passive"))
      (node (ref "R26") (pin "1") (pinfunction "1_1") (pintype "passive"))
    )
    (net (code "112") (name "Net-(Q11-PadB)") (class "Default")
      (node (ref "Q11") (pin "B") (pinfunction "B_B") (pintype "passive"))
      (node (ref "Q12") (pin "B") (pinfunction "B_B") (pintype "passive"))
      (node (ref "Q12") (pin "C") (pinfunction "C_C") (pintype "passive"))
      (node (ref "R28") (pin "1") (pinfunction "1_1") (pintype "passive"))
    )
    (net (code "113") (name "Net-(Q13-PadB)") (class "Default")
      (node (ref "Q13") (pin "B") (pinfunction "B_B") (pintype "passive"))
      (node (ref "R31") (pin "2") (pinfunction "2_2") (pintype "passive"))
    )
    (net (code "114") (name "Net-(Q15-D)") (class "Default")
      (node (ref "Q15") (pin "3") (pinfunction "D_3") (pintype "passive"))
      (node (ref "R30") (pin "1") (pinfunction "1_1") (pintype "passive"))
    )
    (net (code "115") (name "Net-(R10-Pad2)") (class "Default")
      (node (ref "R10") (pin "2") (pinfunction "2_2") (pintype "passive"))
      (node (ref "R3") (pin "1") (pinfunction "1_1") (pintype "passive"))
      (node (ref "R4") (pin "2") (pinfunction "2_2") (pintype "passive"))
      (node (ref "R7") (pin "2") (pinfunction "2_2") (pintype "passive"))
      (node (ref "R8") (pin "2") (pinfunction "2_2") (pintype "passive"))
      (node (ref "R9") (pin "2") (pinfunction "2_2") (pintype "passive"))
    )
    (net (code "116") (name "Net-(U$1-PA4{slash}SPI1_NSS{slash}SPI3_NSS)") (class "Default")
      (node (ref "R69") (pin "1") (pinfunction "1_1") (pintype "passive"))
      (node (ref "U$1") (pin "P$29") (pinfunction "PA4/SPI1_NSS/SPI3_NSS_P$29") (pintype "bidirectional"))
    )
    (net (code "117") (name "Net-(U$1-PA5{slash}SPI1_SCK)") (class "Default")
      (node (ref "R70") (pin "1") (pinfunction "1_1") (pintype "passive"))
      (node (ref "U$1") (pin "P$30") (pinfunction "PA5/SPI1_SCK_P$30") (pintype "bidirectional"))
    )
    (net (code "118") (name "Net-(U$1-PA13{slash}SWDIO)") (class "Default")
      (node (ref "SWDIO") (pin "2") (pinfunction "2_2") (pintype "passive"))
      (node (ref "U$1") (pin "P$72") (pinfunction "PA13/SWDIO_P$72") (pintype "bidirectional"))
    )
    (net (code "119") (name "Net-(U$1-PA14{slash}SWCLK)") (class "Default")
      (node (ref "SWDIO") (pin "4") (pinfunction "4_4") (pintype "passive"))
      (node (ref "U$1") (pin "P$76") (pinfunction "PA14/SWCLK_P$76") (pintype "bidirectional"))
    )
    (net (code "120") (name "Net-(U$1-PB6{slash}I2C1_SCL{slash}USART1_TX{slash}CAN2_TX)") (class "Default")
      (node (ref "U$1") (pin "P$92") (pinfunction "PB6/I2C1_SCL/USART1_TX/CAN2_TX_P$92") (pintype "bidirectional"))
      (node (ref "UART") (pin "2") (pinfunction "2_2") (pintype "passive"))
    )
    (net (code "121") (name "Net-(U$1-PB7{slash}I2C1_SDA{slash}USART1_RX)") (class "Default")
      (node (ref "U$1") (pin "P$93") (pinfunction "PB7/I2C1_SDA/USART1_RX_P$93") (pintype "bidirectional"))
      (node (ref "UART") (pin "3") (pinfunction "3_3") (pintype "passive"))
    )
    (net (code "122") (name "Net-(U$1-PE15)") (class "Default")
      (node (ref "R71") (pin "2") (pinfunction "2_2") (pintype "passive"))
      (node (ref "U$1") (pin "P$46") (pinfunction "PE15_P$46") (pintype "bidirectional"))
    )
    (net (code "123") (name "Net-(U$1-PH0{slash}OSC_IN)") (class "Default")
      (node (ref "C16") (pin "2") (pinfunction "2_2") (pintype "passive"))
      (node (ref "U$1") (pin "P$12") (pinfunction "PH0/OSC_IN_P$12") (pintype "bidirectional"))
      (node (ref "Y1") (pin "3") (pinfunction "2_3") (pintype "passive"))
    )
    (net (code "124") (name "Net-(U$1-PH1{slash}OSC_OUT)") (class "Default")
      (node (ref "C15") (pin "2") (pinfunction "2_2") (pintype "passive"))
      (node (ref "U$1") (pin "P$13") (pinfunction "PH1/OSC_OUT_P$13") (pintype "bidirectional"))
      (node (ref "Y1") (pin "1") (pinfunction "1_1") (pintype "passive"))
    )
    (net (code "125") (name "Net-(U$1-VCAP_1)") (class "Default")
      (node (ref "C27") (pin "1") (pinfunction "1_1") (pintype "passive"))
      (node (ref "U$1") (pin "P$49") (pinfunction "VCAP_1_P$49") (pintype "bidirectional"))
    )
    (net (code "126") (name "Net-(U$1-VCAP_2)") (class "Default")
      (node (ref "C7") (pin "1") (pinfunction "1_1") (pintype "passive"))
      (node (ref "U$1") (pin "P$73") (pinfunction "VCAP_2_P$73") (pintype "bidirectional"))
    )
    (net (code "127") (name "Net-(U$1-VREF+)") (class "Default")
      (node (ref "C22") (pin "1") (pinfunction "1_1") (pintype "passive"))
      (node (ref "C29") (pin "1") (pinfunction "1_1") (pintype "passive"))
      (node (ref "R51") (pin "1") (pinfunction "1_1") (pintype "passive"))
      (node (ref "U$1") (pin "P$21") (pinfunction "VREF+_P$21") (pintype "bidirectional"))
    )
    (net (code "128") (name "OUTPUT_ENABLE") (class "Default")
      (node (ref "R31") (pin "1") (pinfunction "1_1") (pintype "passive"))
      (node (ref "U$1") (pin "P$5") (pinfunction "PE6_P$5") (pintype "bidirectional"))
    )
    (net (code "129") (name "PUSHPULL_OUT") (class "Default")
      (node (ref "C28") (pin "2") (pinfunction "2_2") (pintype "passive"))
      (node (ref "C6") (pin "2") (pinfunction "2_2") (pintype "passive"))
      (node (ref "K1") (pin "P") (pinfunction "P_P") (pintype "passive"))
      (node (ref "R11") (pin "2") (pinfunction "2_2") (pintype "passive"))
      (node (ref "R29") (pin "2") (pinfunction "2_2") (pintype "passive"))
      (node (ref "R60") (pin "1") (pinfunction "1_1") (pintype "passive"))
      (node (ref "R7") (pin "1") (pinfunction "1_1") (pintype "passive"))
      (node (ref "R8") (pin "1") (pinfunction "1_1") (pintype "passive"))
      (node (ref "R9") (pin "1") (pinfunction "1_1") (pintype "passive"))
    )
    (net (code "130") (name "SWITCH") (class "Default")
      (node (ref "S1") (pin "1") (pinfunction "P_1") (pintype "passive"))
      (node (ref "U$1") (pin "P$1") (pinfunction "PE2_P$1") (pintype "bidirectional"))
    )
    (net (code "131") (name "USBD_N") (class "Default")
      (node (ref "R64") (pin "2") (pinfunction "2_2") (pintype "passive"))
      (node (ref "U$1") (pin "P$70") (pinfunction "PA11/CAN1_RX_P$70") (pintype "bidirectional"))
    )
    (net (code "132") (name "USBD_P") (class "Default")
      (node (ref "R97") (pin "2") (pinfunction "2_2") (pintype "passive"))
      (node (ref "U$1") (pin "P$71") (pinfunction "PA12/CAN1_TX_P$71") (pintype "bidirectional"))
    )
    (net (code "133") (name "USB_ID") (class "Default")
      (node (ref "R100") (pin "2") (pinfunction "2_2") (pintype "passive"))
      (node (ref "U$1") (pin "P$69") (pinfunction "PA10/USART1_RX_P$69") (pintype "bidirectional"))
    )
    (net (code "134") (name "USB_VBUS") (class "Default")
      (node (ref "C10") (pin "1") (pinfunction "1_1") (pintype "passive"))
      (node (ref "R98") (pin "2") (pinfunction "2_2") (pintype "passive"))
      (node (ref "U$1") (pin "P$68") (pinfunction "PA9/USART1_TX_P$68") (pintype "bidirectional"))
    )
    (net (code "135") (name "VDDA") (class "Default")
      (node (ref "C30") (pin "1") (pinfunction "1_1") (pintype "passive"))
      (node (ref "C31") (pin "1") (pinfunction "1_1") (pintype "passive"))
      (node (ref "L2") (pin "2") (pinfunction "2_2") (pintype "passive"))
      (node (ref "R22") (pin "1") (pinfunction "1_1") (pintype "passive"))
      (node (ref "U$1") (pin "P$22") (pinfunction "VDDA_P$22") (pintype "bidirectional"))
    )
    (net (code "136") (name "VIN") (class "Default")
      (node (ref "C24") (pin "+") (pinfunction "+_+") (pintype "passive"))
      (node (ref "C34") (pin "2") (pinfunction "2_2") (pintype "passive"))
      (node (ref "C49") (pin "1") (pinfunction "1_1") (pintype "passive"))
      (node (ref "IC12") (pin "8") (pinfunction "VCC_8") (pintype "input"))
      (node (ref "IC8") (pin "2") (pinfunction "VIN_2") (pintype "power_in"))
      (node (ref "L9") (pin "1") (pinfunction "1_1") (pintype "passive"))
      (node (ref "PAD1") (pin "1") (pinfunction "P_1") (pintype "passive"))
    )
    (net (code "137") (name "VOLTAGE_CTRL") (class "Default")
      (node (ref "IC7") (pin "10") (pinfunction "+IN_10") (pintype "input"))
      (node (ref "R69") (pin "2") (pinfunction "2_2") (pintype "passive"))
    )
    (net (code "138") (name "VOLTAGE_RANGE_SEL") (class "Default")
      (node (ref "Q15") (pin "1") (pinfunction "G_1") (pintype "passive"))
      (node (ref "U$1") (pin "P$38") (pinfunction "PE7_P$38") (pintype "bidirectional"))
    )
    (net (code "139") (name "VOUT_HIGHSIDE") (class "Default")
      (node (ref "Q2") (pin "E") (pinfunction "E_E") (pintype "passive"))
      (node (ref "Q6") (pin "E") (pinfunction "E_E") (pintype "passive"))
      (node (ref "R1") (pin "1") (pinfunction "1_1") (pintype "passive"))
      (node (ref "R3") (pin "2") (pinfunction "2_2") (pintype "passive"))
      (node (ref "R40") (pin "1") (pinfunction "1_1") (pintype "passive"))
    )
    (net (code "140") (name "VSUPPLY_HIGHSIDE") (class "Default")
      (node (ref "C25") (pin "+") (pinfunction "+_+") (pintype "passive"))
      (node (ref "C26") (pin "+") (pinfunction "+_+") (pintype "passive"))
      (node (ref "L1") (pin "2") (pinfunction "2_2") (pintype "passive"))
      (node (ref "Q2") (pin "C") (pinfunction "C_C") (pintype "passive"))
      (node (ref "Q4") (pin "E") (pinfunction "E_E") (pintype "passive"))
      (node (ref "R2") (pin "2") (pinfunction "2_2") (pintype "passive"))
      (node (ref "R38") (pin "2") (pinfunction "2_2") (pintype "passive"))
      (node (ref "R58") (pin "1") (pinfunction "1_1") (pintype "passive"))
    )
    (net (code "141") (name "VSUPPLY_LOWSIDE") (class "Default")
      (node (ref "IC10") (pin "3") (pinfunction "+IN_3") (pintype "input"))
      (node (ref "Q1") (pin "C") (pinfunction "C_C") (pintype "passive"))
      (node (ref "Q3") (pin "E") (pinfunction "E_E") (pintype "passive"))
      (node (ref "R45") (pin "2") (pinfunction "2_2") (pintype "passive"))
      (node (ref "R6") (pin "2") (pinfunction "2_2") (pintype "passive"))
    )
    (net (code "142") (name "unconnected-(D9-C2-Pad2)") (class "Default")
      (node (ref "D9") (pin "2") (pinfunction "C2_2") (pintype "passive"))
    )
    (net (code "143") (name "unconnected-(IC1-ON1-Pad1)") (class "Default")
      (node (ref "IC1") (pin "1") (pinfunction "ON1_1") (pintype "passive"))
    )
    (net (code "144") (name "unconnected-(IC1-ON2-Pad8)") (class "Default")
      (node (ref "IC1") (pin "8") (pinfunction "ON2_8") (pintype "passive"))
    )
    (net (code "145") (name "unconnected-(IC1-OPT-Pad5)") (class "Default")
      (node (ref "IC1") (pin "5") (pinfunction "OPT_5") (pintype "passive"))
    )
    (net (code "146") (name "unconnected-(IC2-ON1-Pad1)") (class "Default")
      (node (ref "IC2") (pin "1") (pinfunction "ON1_1") (pintype "passive"))
    )
    (net (code "147") (name "unconnected-(IC2-ON2-Pad8)") (class "Default")
      (node (ref "IC2") (pin "8") (pinfunction "ON2_8") (pintype "passive"))
    )
    (net (code "148") (name "unconnected-(IC2-OPT-Pad5)") (class "Default")
      (node (ref "IC2") (pin "5") (pinfunction "OPT_5") (pintype "passive"))
    )
    (net (code "149") (name "unconnected-(IC5-ON1-Pad1)") (class "Default")
      (node (ref "IC5") (pin "1") (pinfunction "ON1_1") (pintype "passive"))
    )
    (net (code "150") (name "unconnected-(IC5-ON2-Pad8)") (class "Default")
      (node (ref "IC5") (pin "8") (pinfunction "ON2_8") (pintype "passive"))
    )
    (net (code "151") (name "unconnected-(IC5-OPT-Pad5)") (class "Default")
      (node (ref "IC5") (pin "5") (pinfunction "OPT_5") (pintype "passive"))
    )
    (net (code "152") (name "unconnected-(IC10-ON1-Pad1)") (class "Default")
      (node (ref "IC10") (pin "1") (pinfunction "ON1_1") (pintype "passive"))
    )
    (net (code "153") (name "unconnected-(IC10-ON2-Pad8)") (class "Default")
      (node (ref "IC10") (pin "8") (pinfunction "ON2_8") (pintype "passive"))
    )
    (net (code "154") (name "unconnected-(IC10-OPT-Pad5)") (class "Default")
      (node (ref "IC10") (pin "5") (pinfunction "OPT_5") (pintype "passive"))
    )
    (net (code "155") (name "unconnected-(IC12B-SYNC-Pad2)") (class "Default")
      (node (ref "IC12") (pin "2") (pinfunction "SYNC_2") (pintype "input"))
    )
    (net (code "156") (name "unconnected-(IC12B-VREF-Pad6)") (class "Default")
      (node (ref "IC12") (pin "6") (pinfunction "VREF_6") (pintype "input"))
    )
    (net (code "157") (name "unconnected-(K1-PadO)") (class "Default")
      (node (ref "K1") (pin "O") (pinfunction "O_O") (pintype "passive"))
    )
    (net (code "158") (name "unconnected-(U$1-PA6{slash}SPI1_MISO-PadP$31)") (class "Default")
      (node (ref "U$1") (pin "P$31") (pinfunction "PA6/SPI1_MISO_P$31") (pintype "bidirectional"))
    )
    (net (code "159") (name "unconnected-(U$1-PA7{slash}SPI1_MOSI-PadP$32)") (class "Default")
      (node (ref "U$1") (pin "P$32") (pinfunction "PA7/SPI1_MOSI_P$32") (pintype "bidirectional"))
    )
    (net (code "160") (name "unconnected-(U$1-PA8{slash}I2C3_SCL-PadP$67)") (class "Default")
      (node (ref "U$1") (pin "P$67") (pinfunction "PA8/I2C3_SCL_P$67") (pintype "bidirectional"))
    )
    (net (code "161") (name "unconnected-(U$1-PA15{slash}SPI1_NSS{slash}SPI3_NSS-PadP$77)") (class "Default")
      (node (ref "U$1") (pin "P$77") (pinfunction "PA15/SPI1_NSS/SPI3_NSS_P$77") (pintype "bidirectional"))
    )
    (net (code "162") (name "unconnected-(U$1-PB0-PadP$35)") (class "Default")
      (node (ref "U$1") (pin "P$35") (pinfunction "PB0_P$35") (pintype "bidirectional"))
    )
    (net (code "163") (name "unconnected-(U$1-PB1-PadP$36)") (class "Default")
      (node (ref "U$1") (pin "P$36") (pinfunction "PB1_P$36") (pintype "bidirectional"))
    )
    (net (code "164") (name "unconnected-(U$1-PB2-PadP$37)") (class "Default")
      (node (ref "U$1") (pin "P$37") (pinfunction "PB2_P$37") (pintype "bidirectional"))
    )
    (net (code "165") (name "unconnected-(U$1-PB10{slash}I2C2_SCL{slash}SPI2_SCK{slash}USART3_TX-PadP$47)") (class "Default")
      (node (ref "U$1") (pin "P$47") (pinfunction "PB10/I2C2_SCL/SPI2_SCK/USART3_TX_P$47") (pintype "bidirectional"))
    )
    (net (code "166") (name "unconnected-(U$1-PB11{slash}I2C2_SDA{slash}USART3_RX-PadP$48)") (class "Default")
      (node (ref "U$1") (pin "P$48") (pinfunction "PB11/I2C2_SDA/USART3_RX_P$48") (pintype "bidirectional"))
    )
    (net (code "167") (name "unconnected-(U$1-PB12{slash}SPI2_NSS{slash}CAN2_RX-PadP$51)") (class "Default")
      (node (ref "U$1") (pin "P$51") (pinfunction "PB12/SPI2_NSS/CAN2_RX_P$51") (pintype "bidirectional"))
    )
    (net (code "168") (name "unconnected-(U$1-PB13{slash}SPI2_SCK{slash}CAN2_TX-PadP$52)") (class "Default")
      (node (ref "U$1") (pin "P$52") (pinfunction "PB13/SPI2_SCK/CAN2_TX_P$52") (pintype "bidirectional"))
    )
    (net (code "169") (name "unconnected-(U$1-PB14{slash}SPI2_MISO-PadP$53)") (class "Default")
      (node (ref "U$1") (pin "P$53") (pinfunction "PB14/SPI2_MISO_P$53") (pintype "bidirectional"))
    )
    (net (code "170") (name "unconnected-(U$1-PB15{slash}SPI2_MOSI-PadP$54)") (class "Default")
      (node (ref "U$1") (pin "P$54") (pinfunction "PB15/SPI2_MOSI_P$54") (pintype "bidirectional"))
    )
    (net (code "171") (name "unconnected-(U$1-PC0-PadP$15)") (class "Default")
      (node (ref "U$1") (pin "P$15") (pinfunction "PC0_P$15") (pintype "bidirectional"))
    )
    (net (code "172") (name "unconnected-(U$1-PC1-PadP$16)") (class "Default")
      (node (ref "U$1") (pin "P$16") (pinfunction "PC1_P$16") (pintype "bidirectional"))
    )
    (net (code "173") (name "unconnected-(U$1-PC4-PadP$33)") (class "Default")
      (node (ref "U$1") (pin "P$33") (pinfunction "PC4_P$33") (pintype "bidirectional"))
    )
    (net (code "174") (name "unconnected-(U$1-PC5-PadP$34)") (class "Default")
      (node (ref "U$1") (pin "P$34") (pinfunction "PC5_P$34") (pintype "bidirectional"))
    )
    (net (code "175") (name "unconnected-(U$1-PC6{slash}USART6_TX-PadP$63)") (class "Default")
      (node (ref "U$1") (pin "P$63") (pinfunction "PC6/USART6_TX_P$63") (pintype "bidirectional"))
    )
    (net (code "176") (name "unconnected-(U$1-PC13-PadP$7)") (class "Default")
      (node (ref "U$1") (pin "P$7") (pinfunction "PC13_P$7") (pintype "bidirectional"))
    )
    (net (code "177") (name "unconnected-(U$1-PC14-PadP$8)") (class "Default")
      (node (ref "U$1") (pin "P$8") (pinfunction "PC14_P$8") (pintype "bidirectional"))
    )
    (net (code "178") (name "unconnected-(U$1-PC15-PadP$9)") (class "Default")
      (node (ref "U$1") (pin "P$9") (pinfunction "PC15_P$9") (pintype "bidirectional"))
    )
    (net (code "179") (name "unconnected-(U$1-PE1-PadP$98)") (class "Default")
      (node (ref "U$1") (pin "P$98") (pinfunction "PE1_P$98") (pintype "bidirectional"))
    )
    (net (code "180") (name "unconnected-(U$1-PE5-PadP$4)") (class "Default")
      (node (ref "U$1") (pin "P$4") (pinfunction "PE5_P$4") (pintype "bidirectional"))
    )
    (net (code "181") (name "unconnected-(U$1-PE8-PadP$39)") (class "Default")
      (node (ref "U$1") (pin "P$39") (pinfunction "PE8_P$39") (pintype "bidirectional"))
    )
    (net (code "182") (name "unconnected-(U$1-PE9-PadP$40)") (class "Default")
      (node (ref "U$1") (pin "P$40") (pinfunction "PE9_P$40") (pintype "bidirectional"))
    )
    (net (code "183") (name "unconnected-(U$1-PE10-PadP$41)") (class "Default")
      (node (ref "U$1") (pin "P$41") (pinfunction "PE10_P$41") (pintype "bidirectional"))
    )
  )
)
